# EK-TM4C1294XL_REV_D.net
KiCad netlist of a schematic drawn in EAGLE
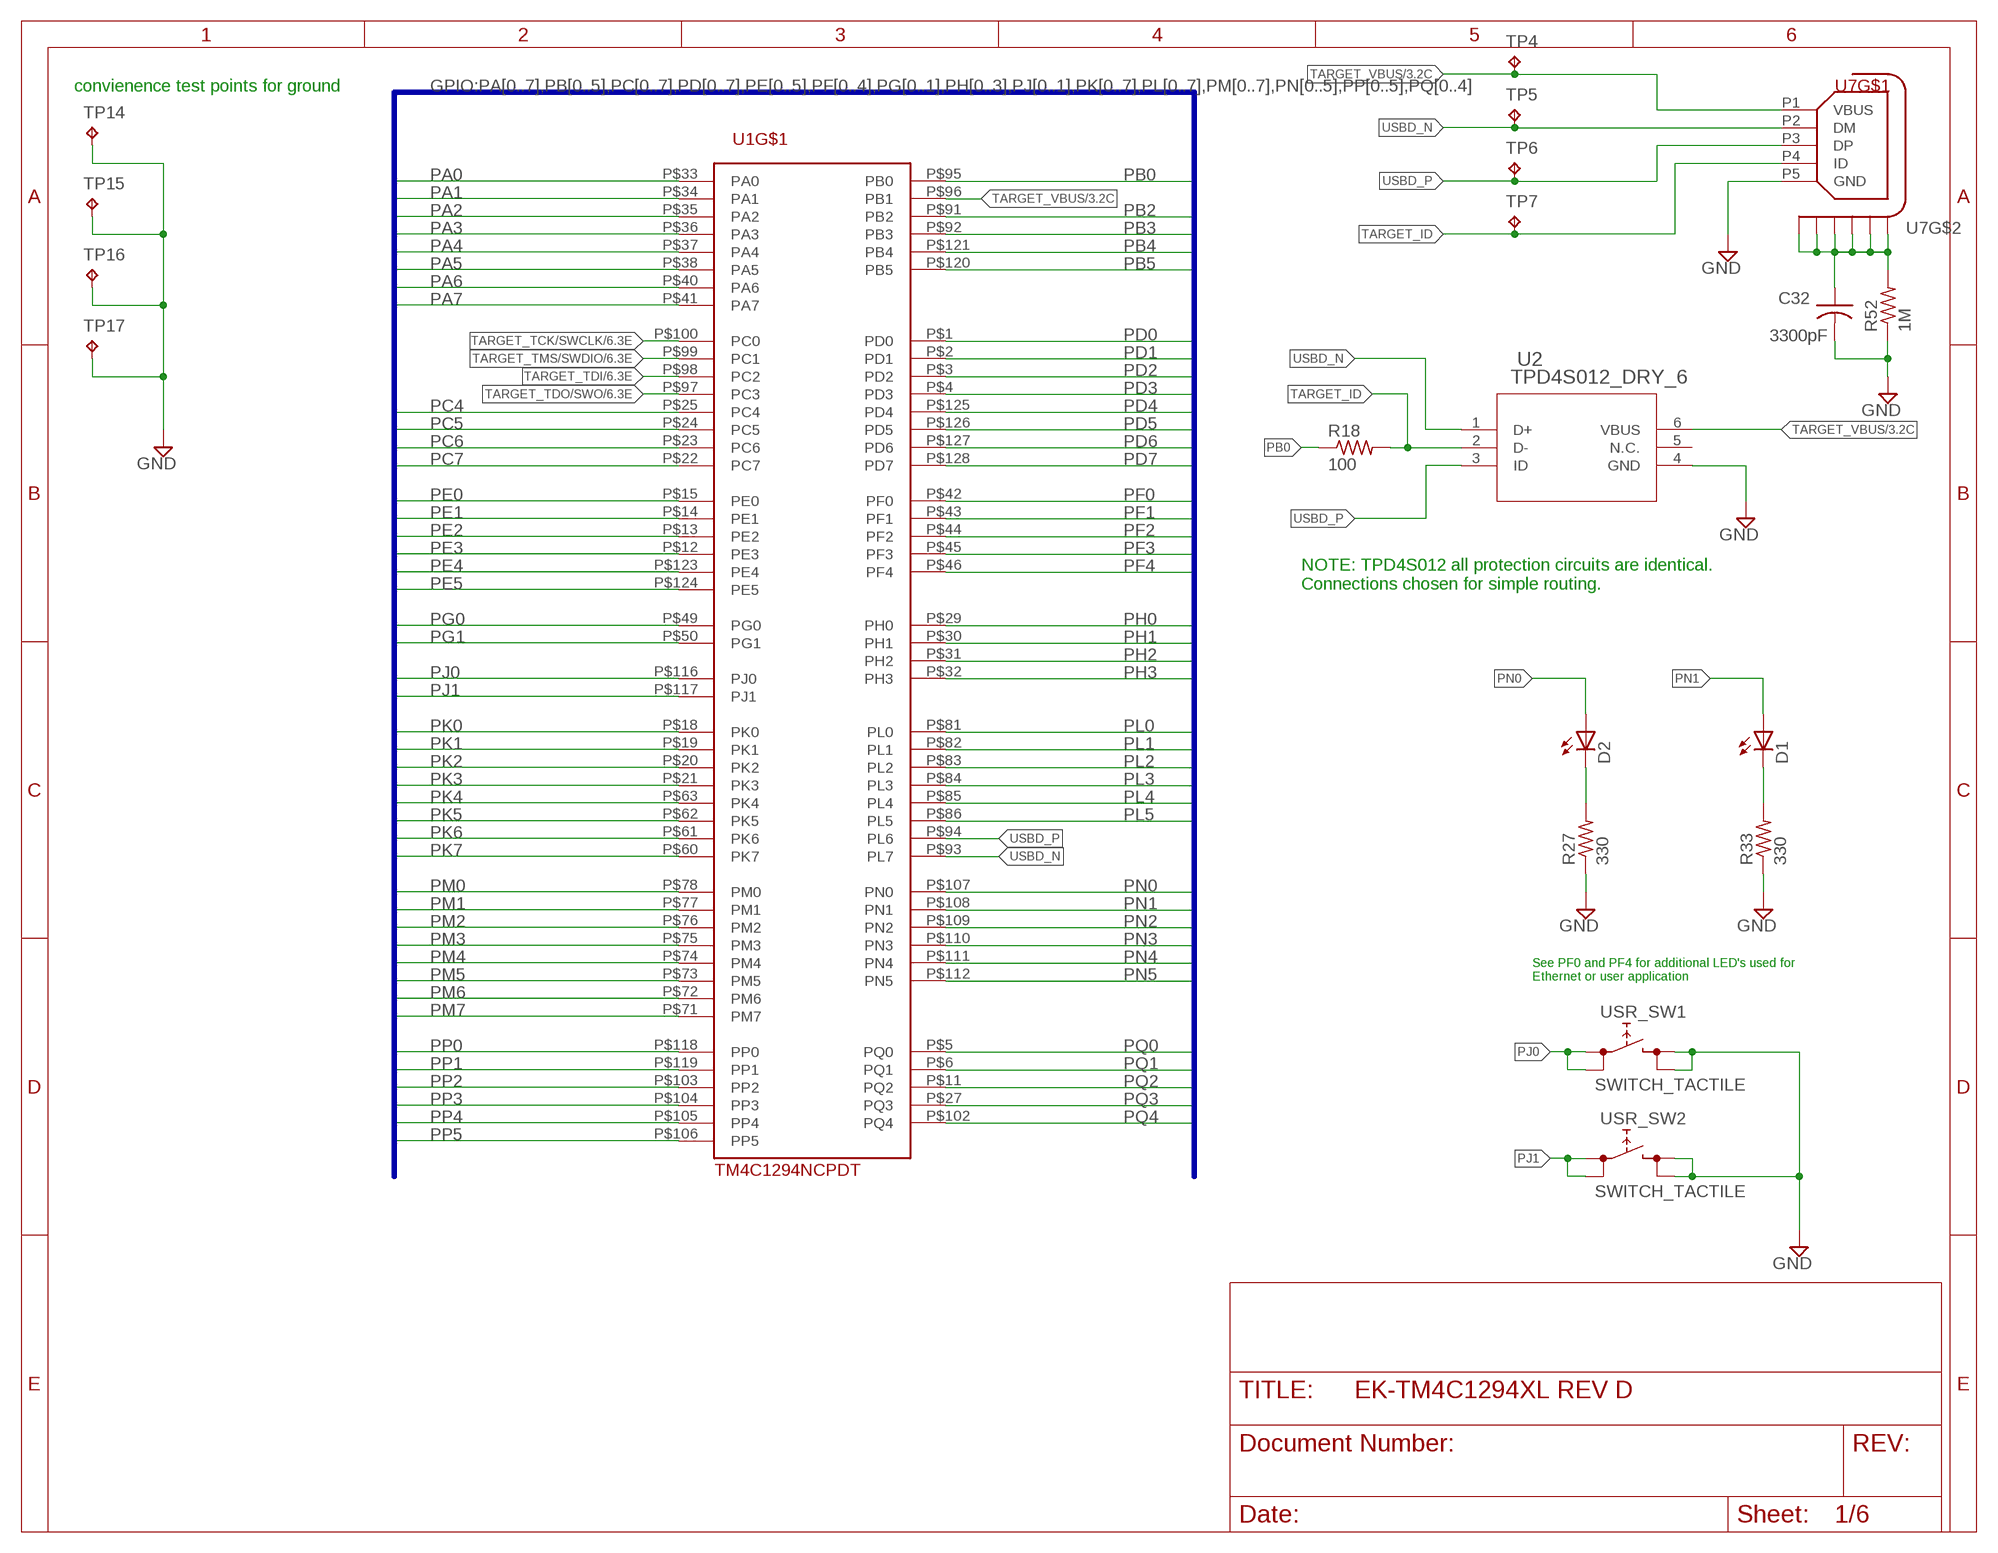
[diagram p0: schematic, sheet 1]
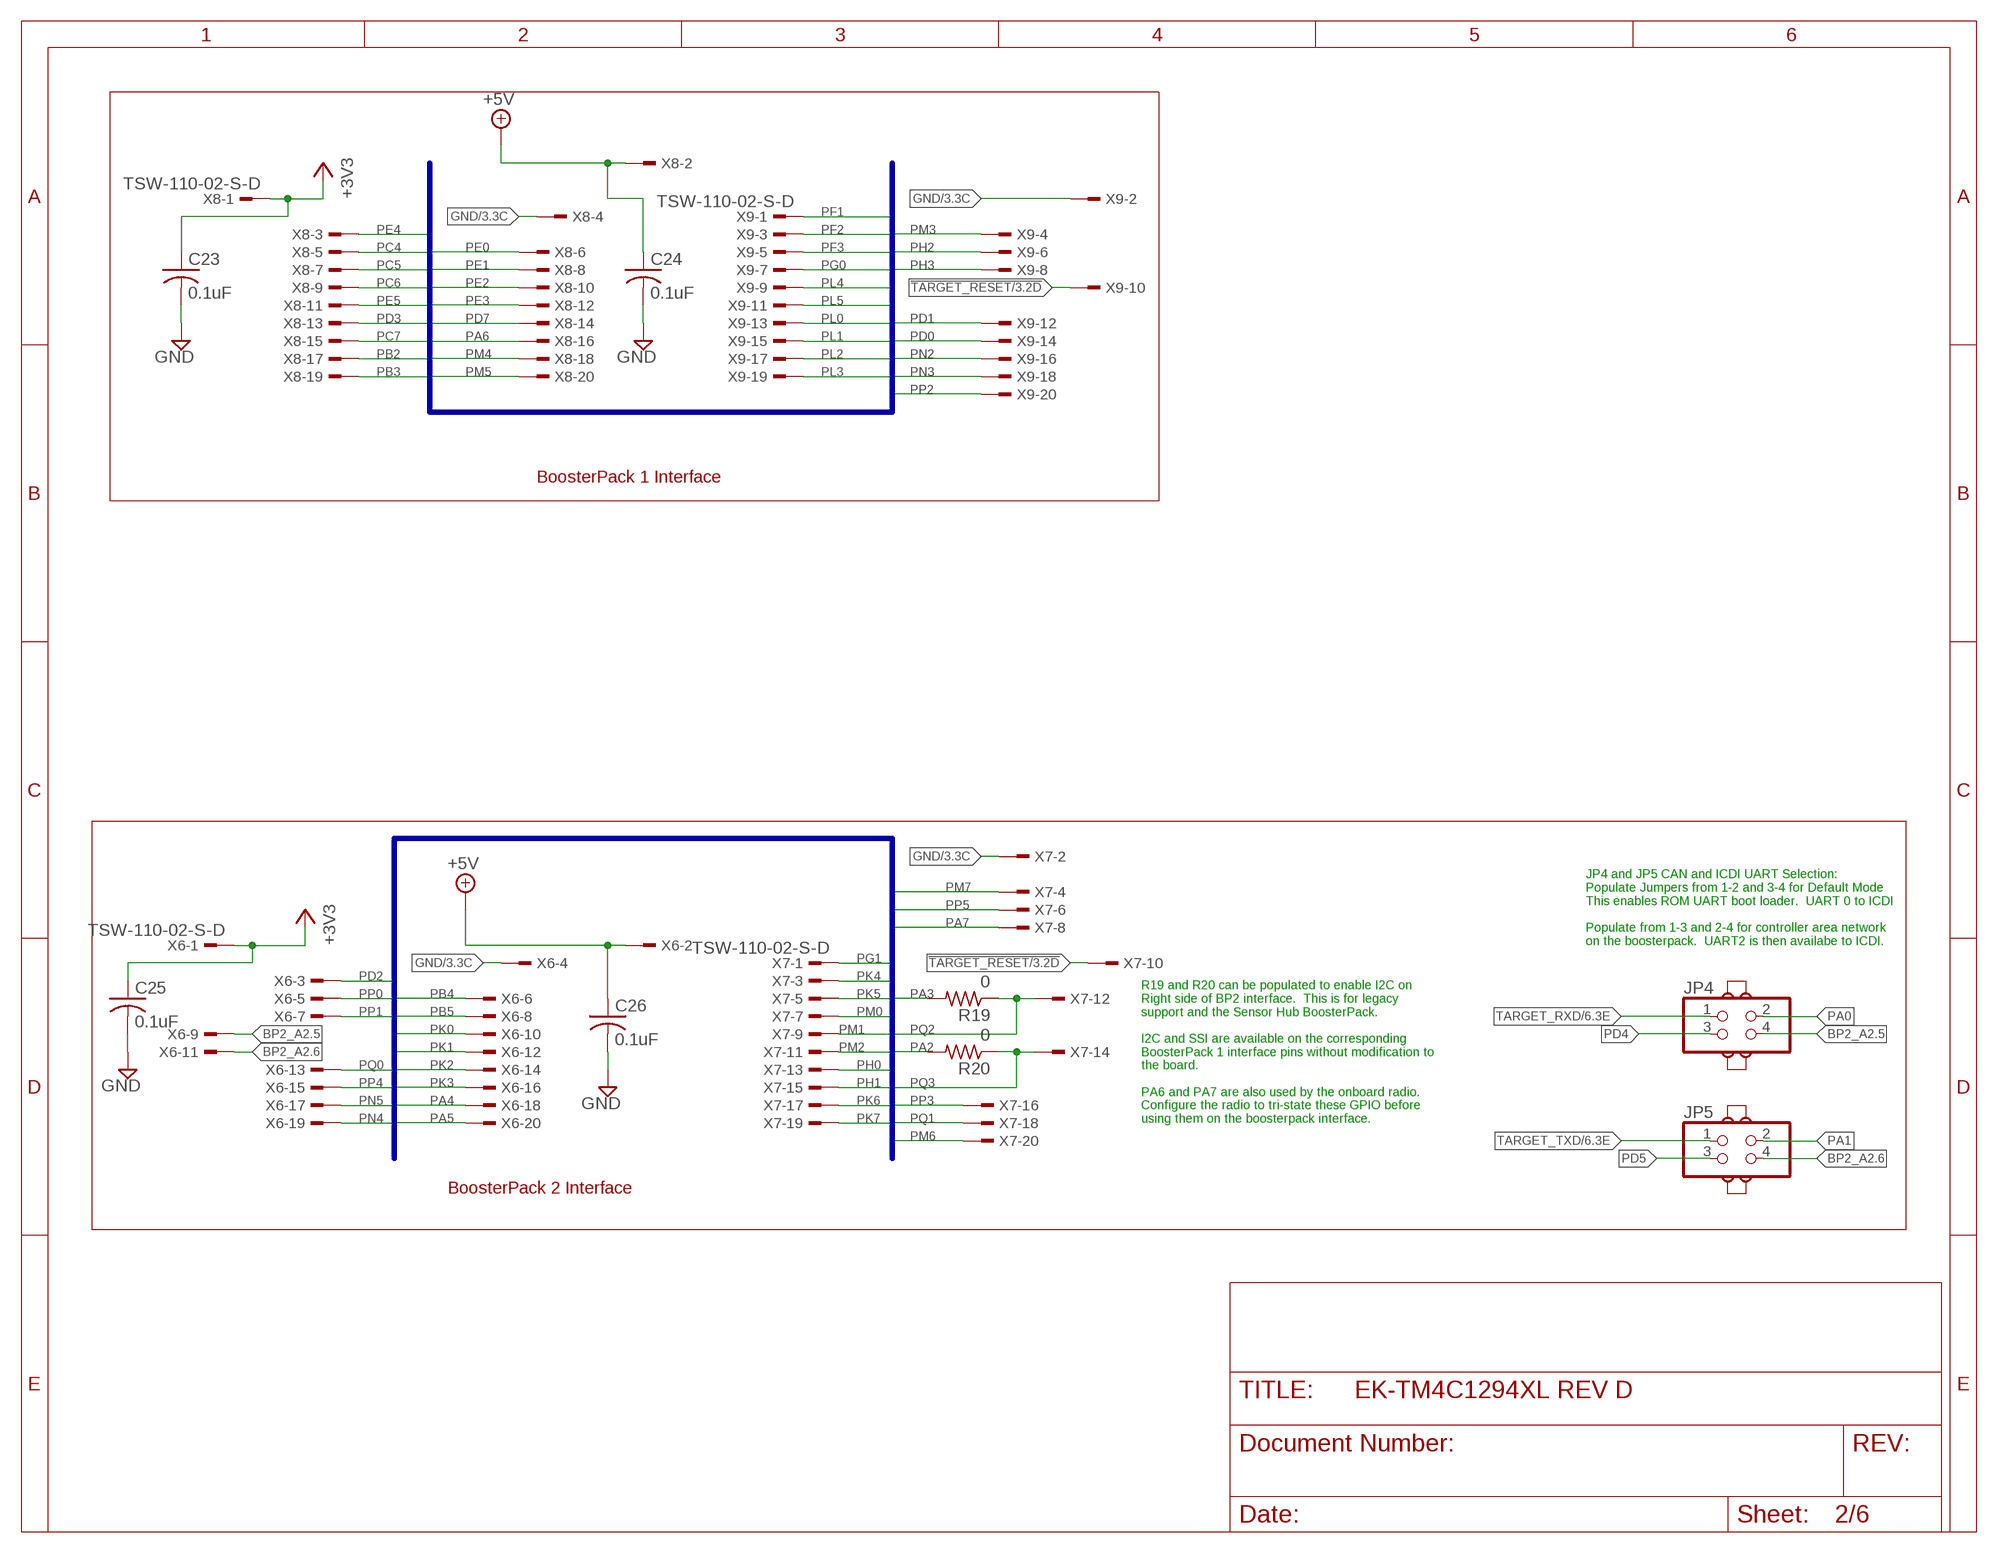
[diagram p1: schematic, sheet 2]
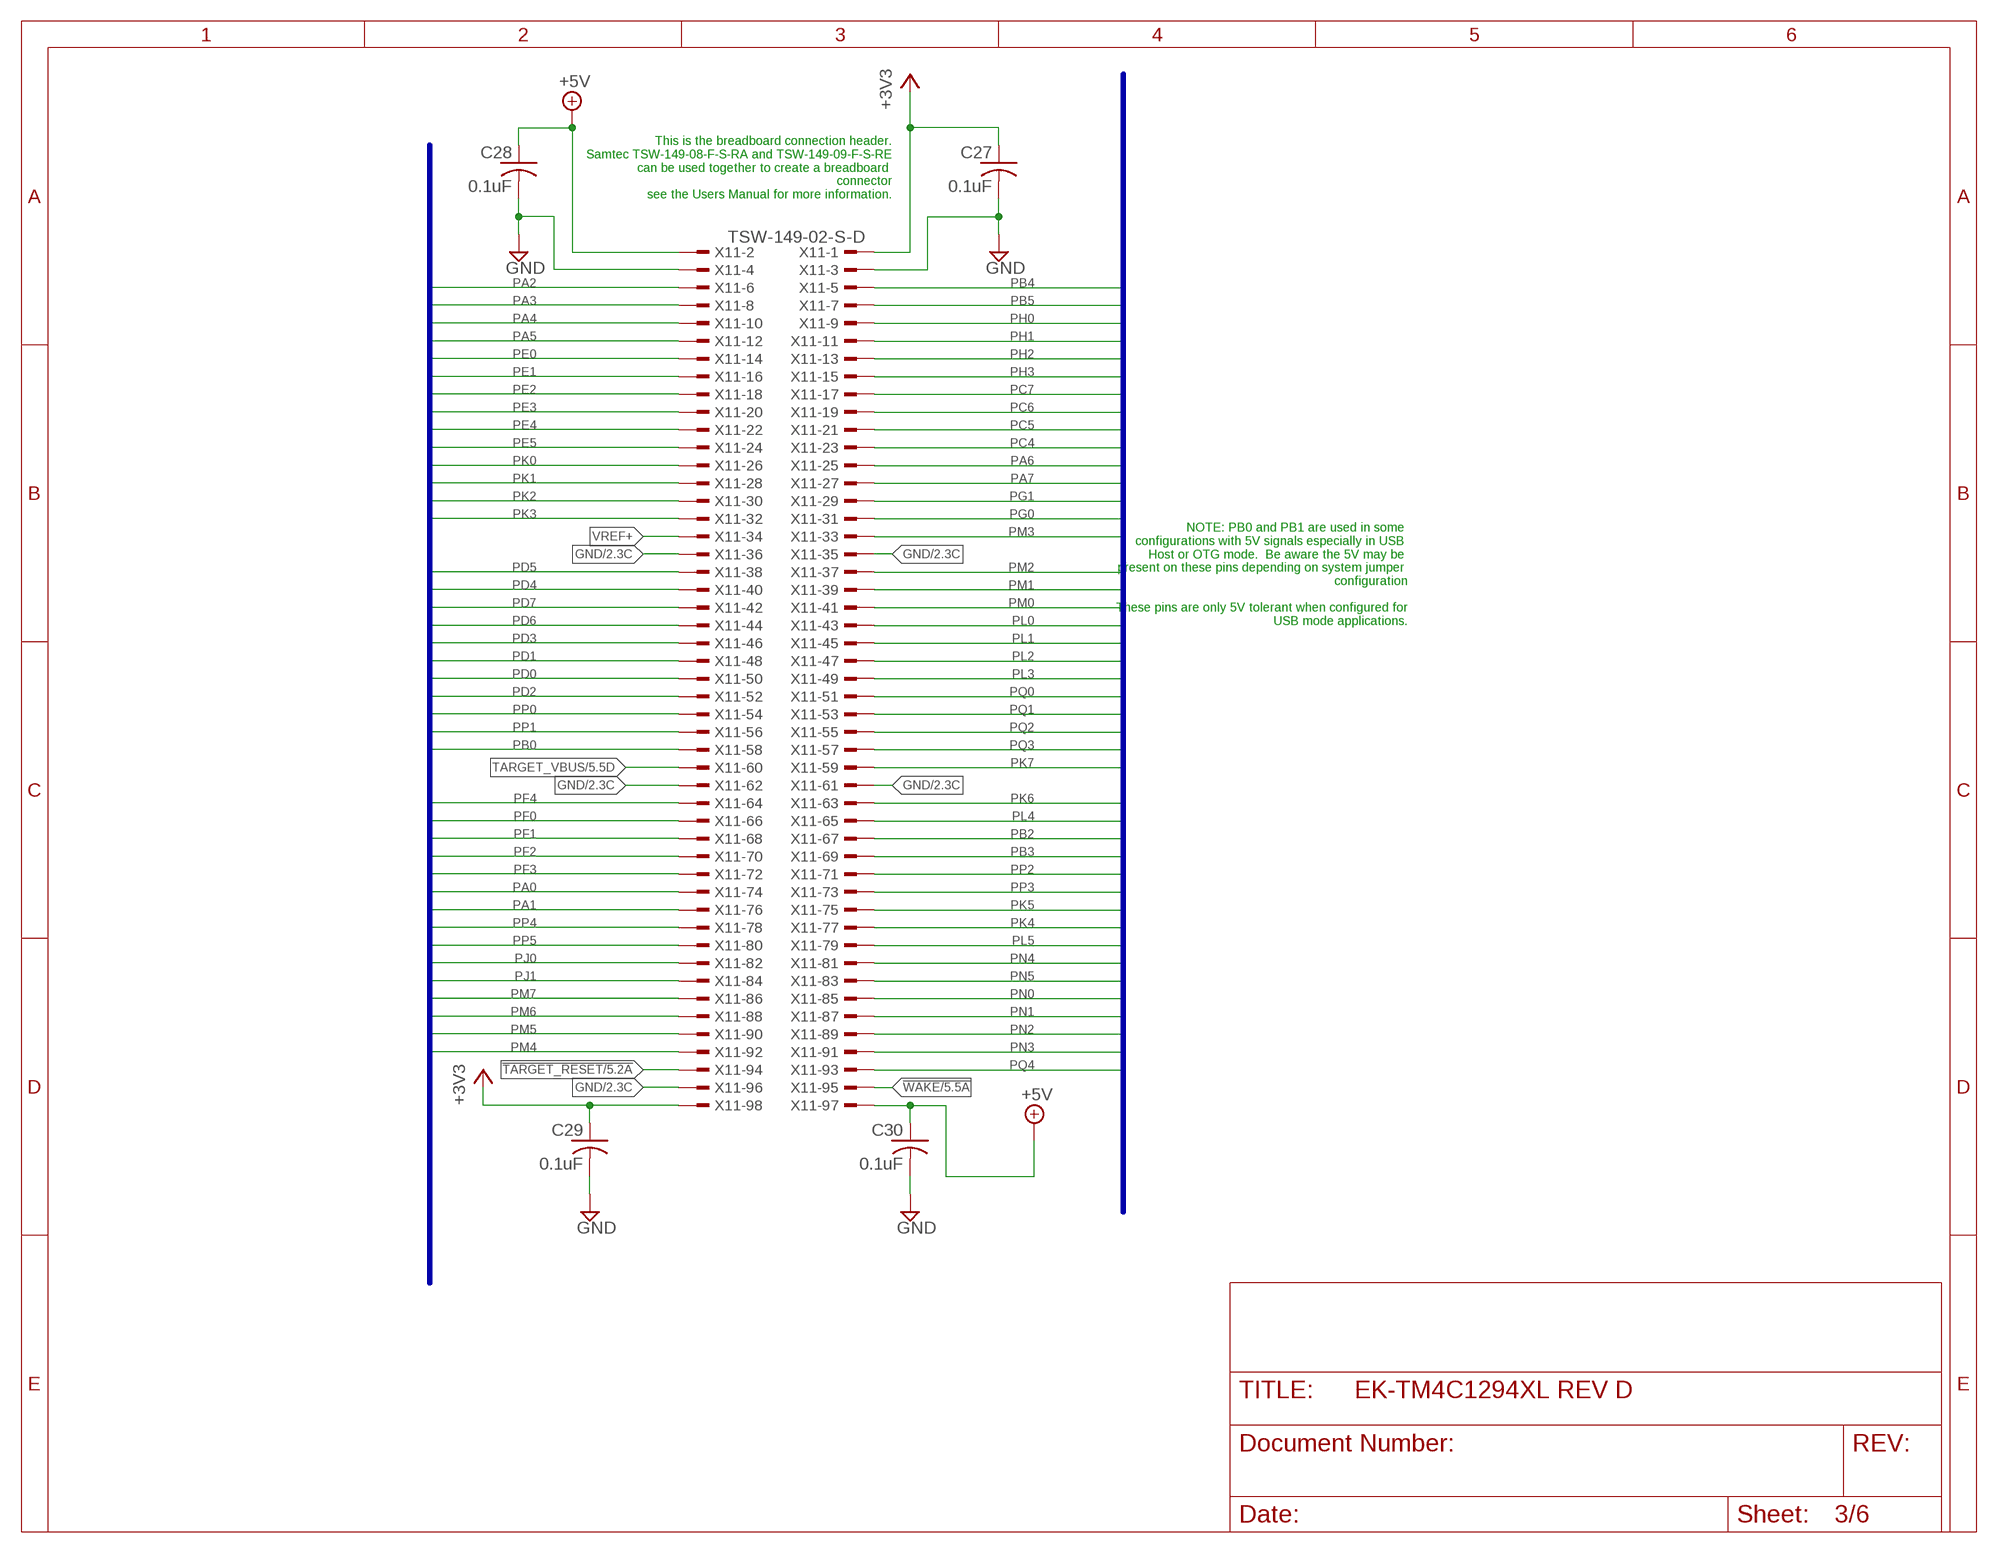
[diagram p2: schematic, sheet 3]
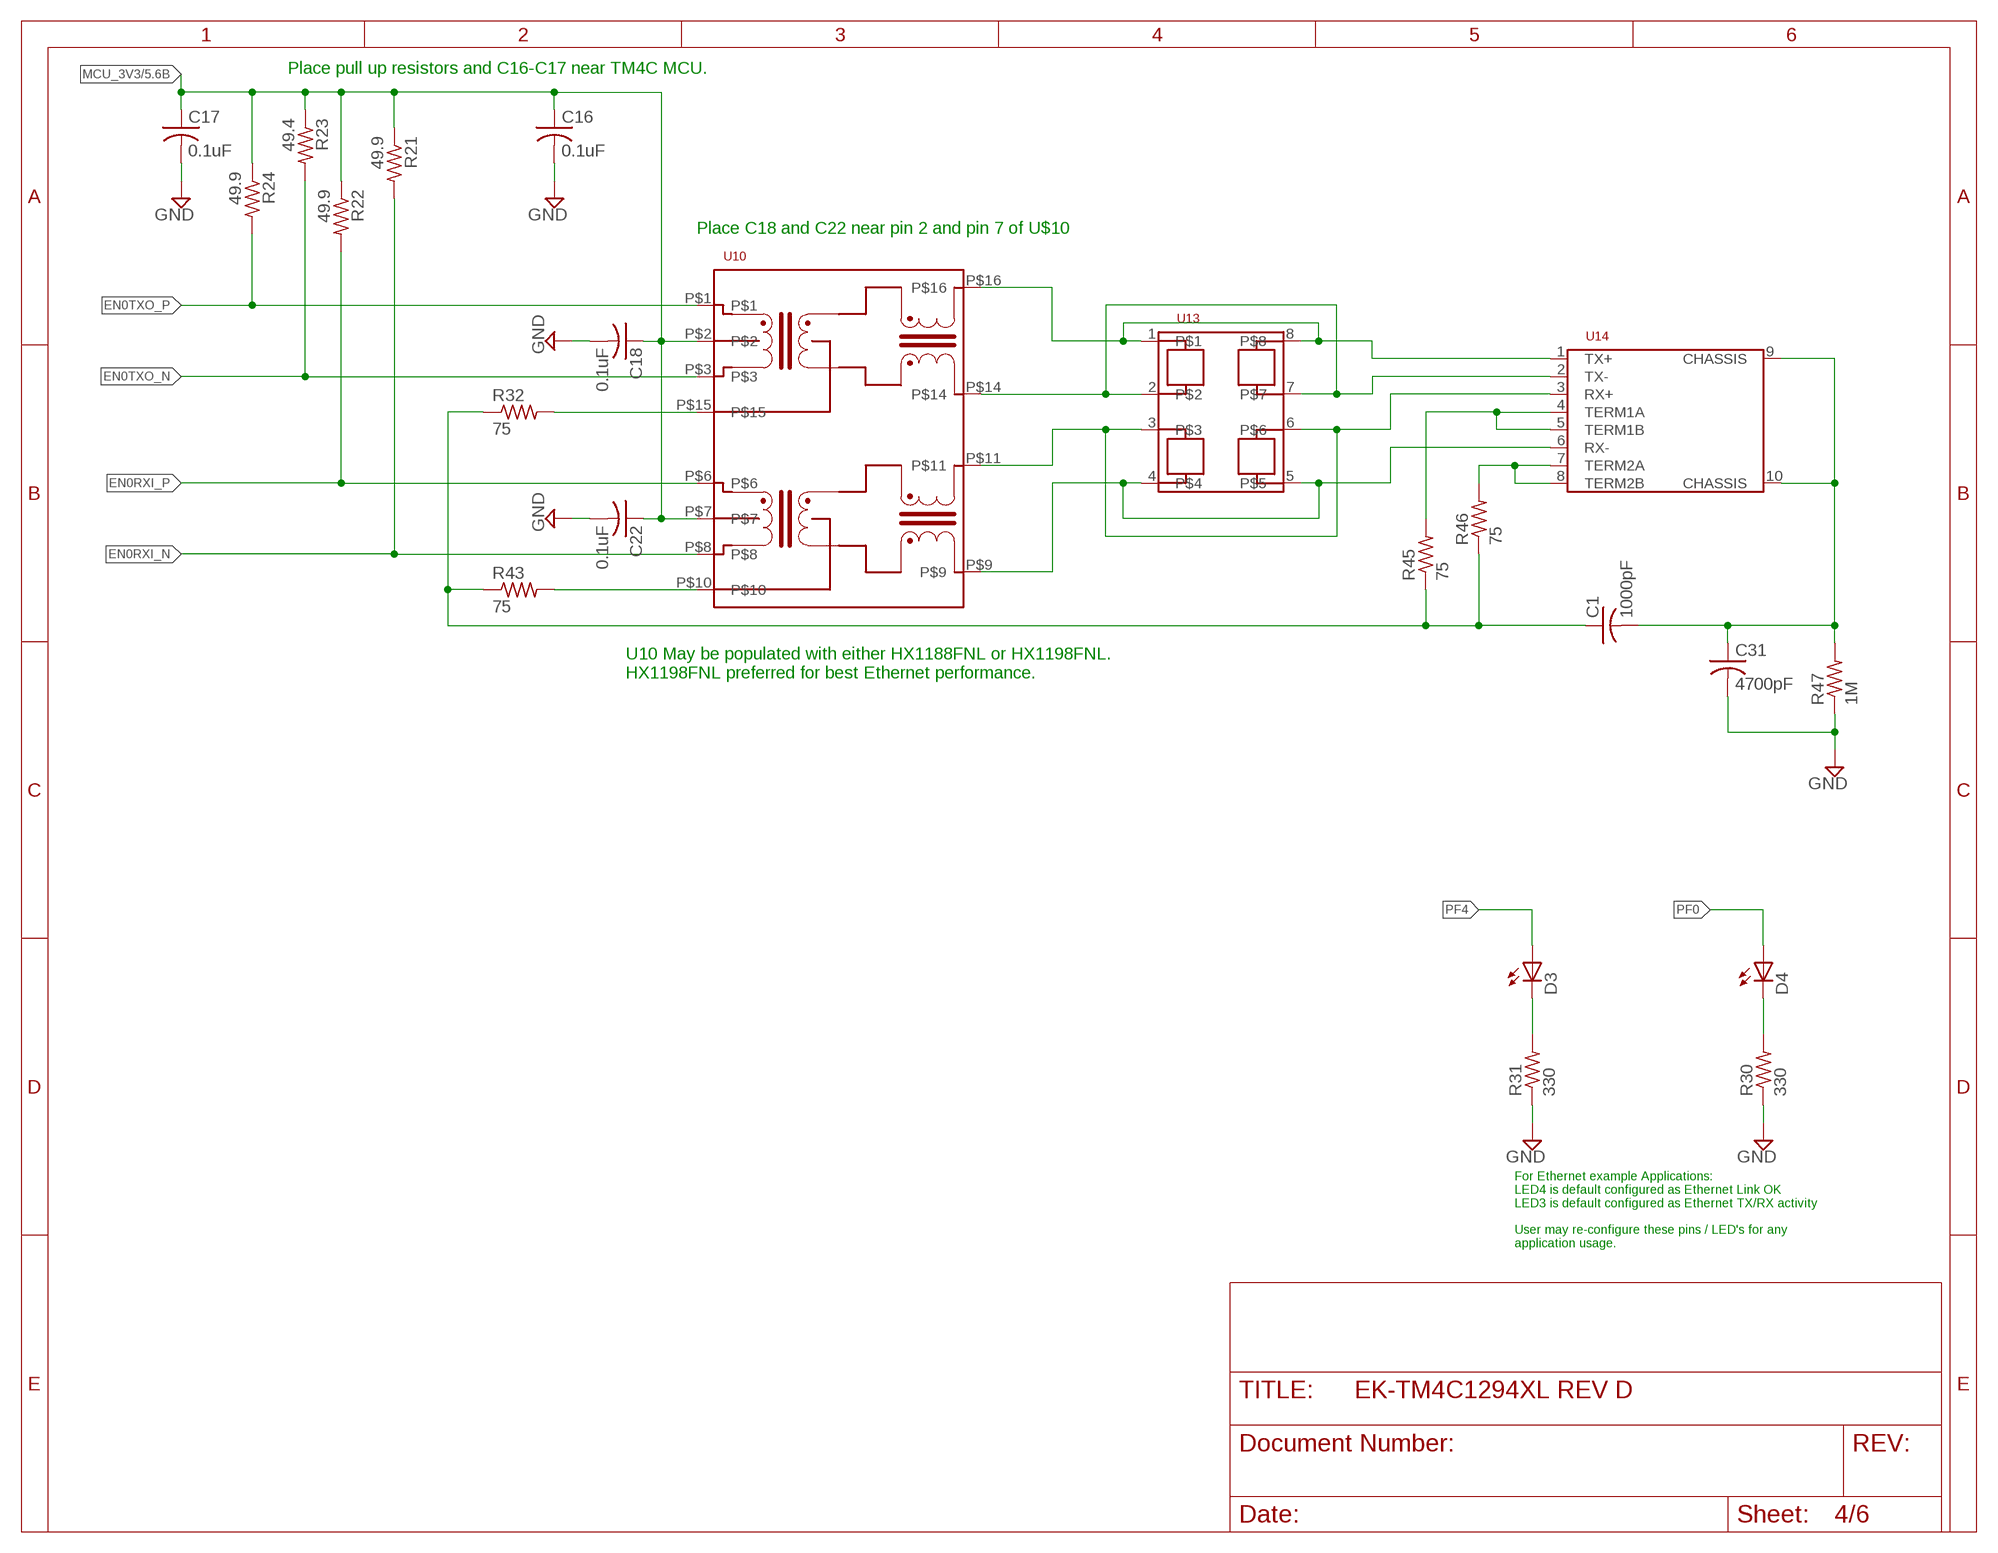
[diagram p3: schematic, sheet 4]
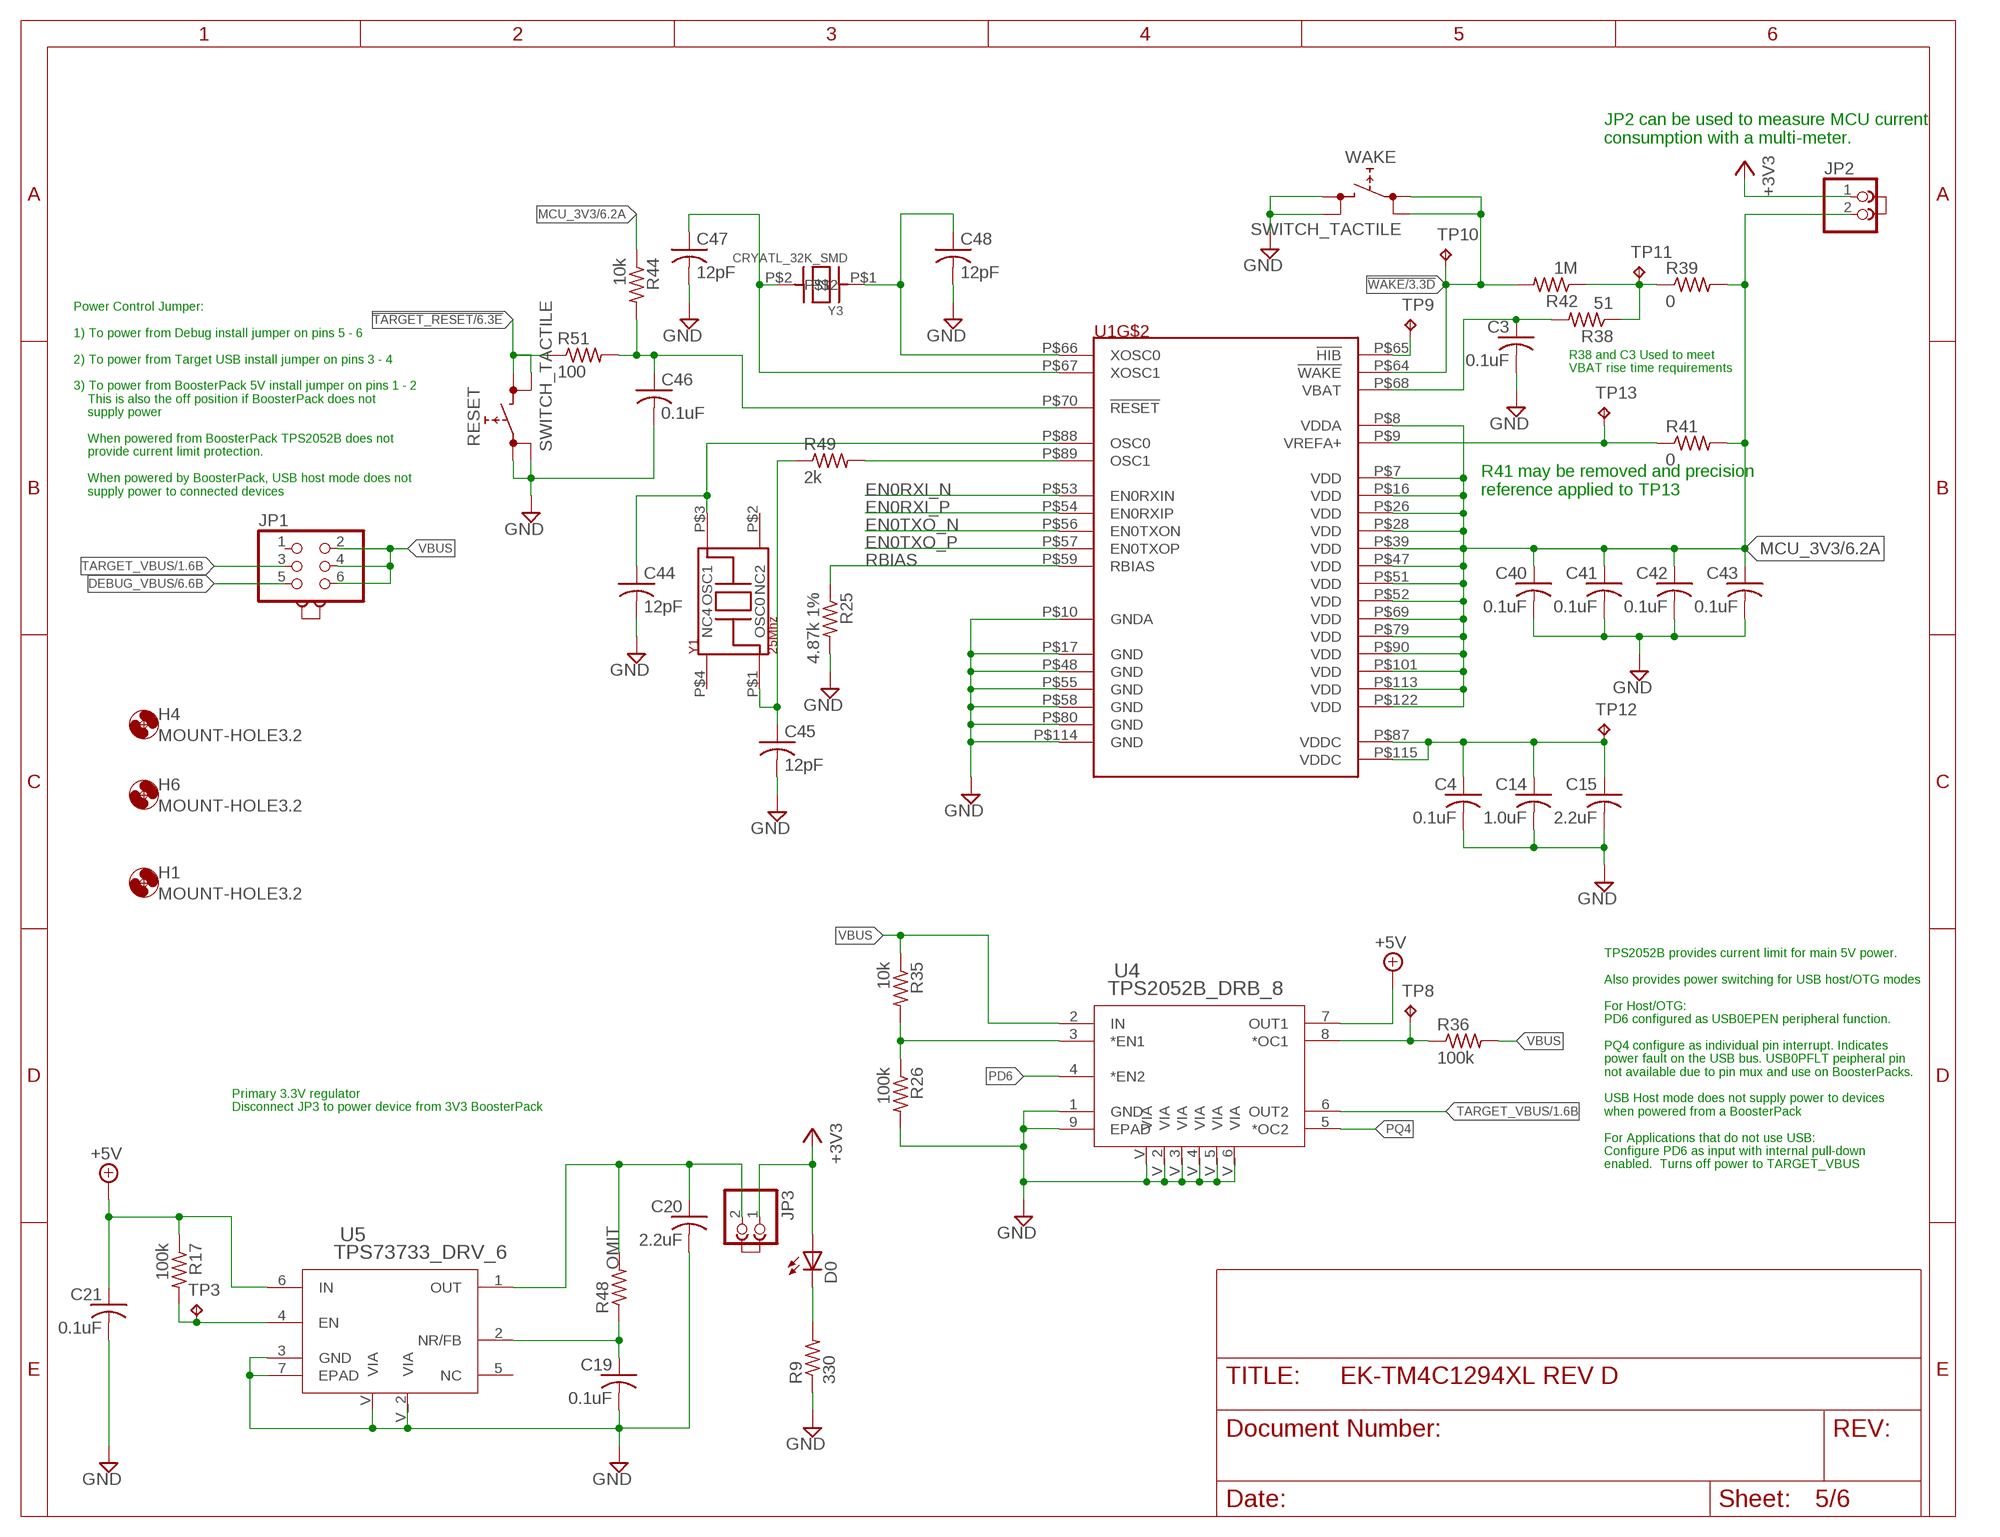
[diagram p4: schematic, sheet 5]
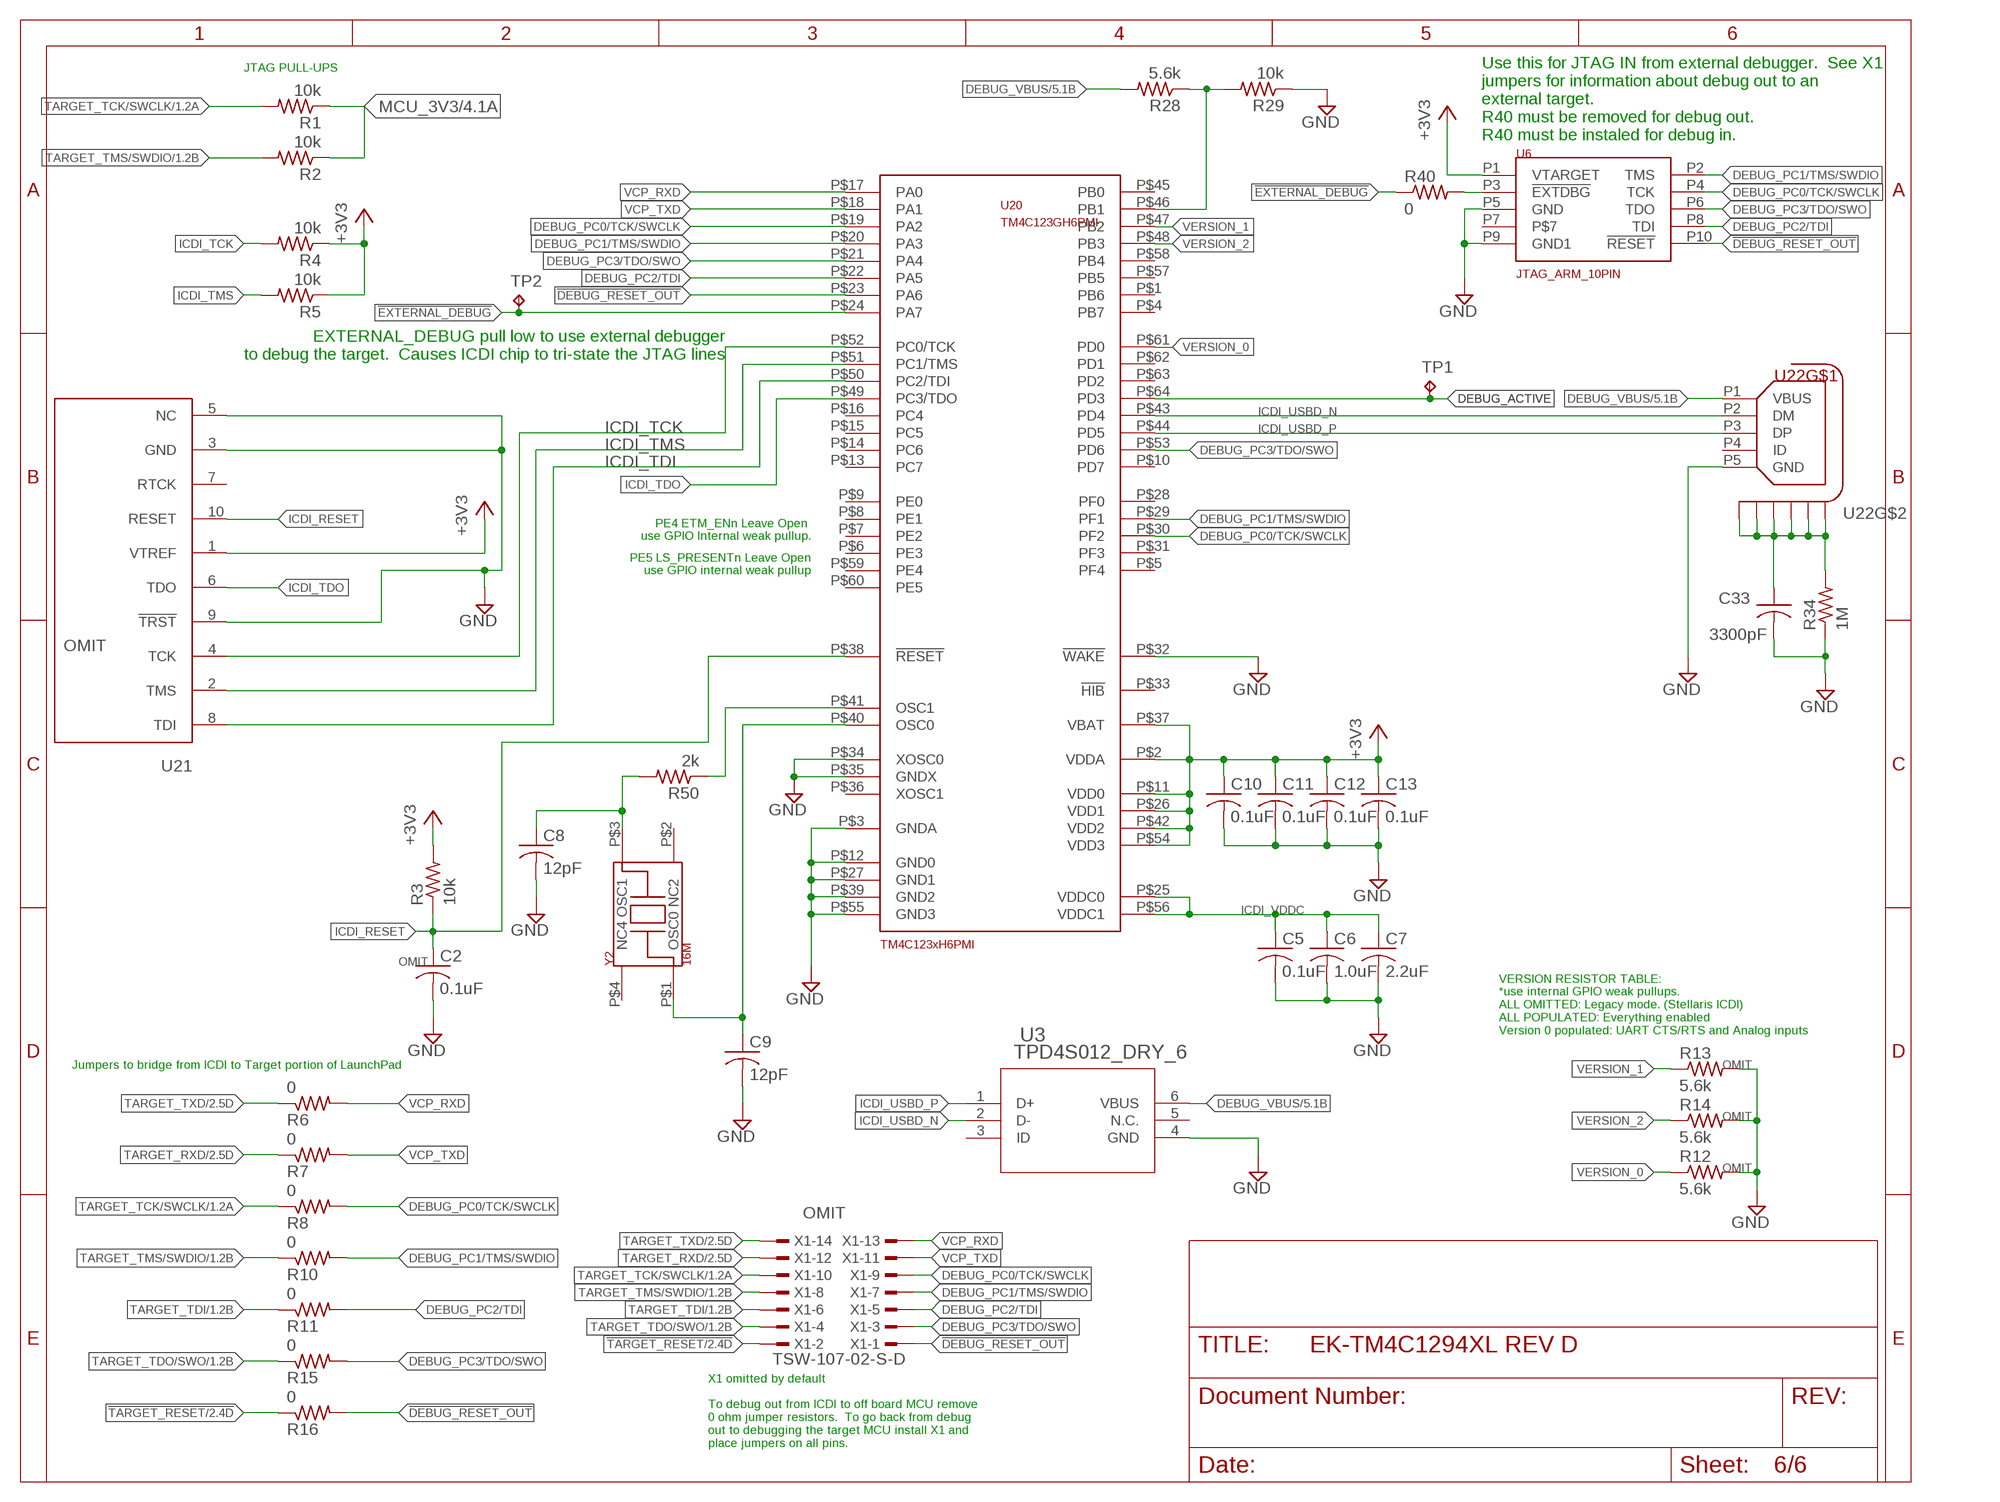
[diagram p5: schematic, sheet 6]

(export (version "E")
  (design (tool "Eeschema 10.0.6"))
  (components
    (comp (ref "C32")
      (value "3300pF")
      (footprint "eagle-import:C0603")
      (libsource (lib "eagle-import") (part "C-USC0603"))
    )
    (comp (ref "D1")
      (value "LEDCHIPLED_0603")
      (footprint "eagle-import:CHIPLED_0603")
      (libsource (lib "eagle-import") (part "LEDCHIPLED_0603"))
    )
    (comp (ref "D2")
      (value "LEDCHIPLED_0603")
      (footprint "eagle-import:CHIPLED_0603")
      (libsource (lib "eagle-import") (part "LEDCHIPLED_0603"))
    )
    (comp (ref "R18")
      (value "100")
      (footprint "eagle-import:R0402")
      (libsource (lib "eagle-import") (part "ek-tm4c129exl_R-US_R0402"))
    )
    (comp (ref "R27")
      (value "330")
      (footprint "eagle-import:R0402")
      (libsource (lib "eagle-import") (part "ek-tm4c129exl_R-US_R0402"))
    )
    (comp (ref "R33")
      (value "330")
      (footprint "eagle-import:R0402")
      (libsource (lib "eagle-import") (part "ek-tm4c129exl_R-US_R0402"))
    )
    (comp (ref "R52")
      (value "1M")
      (footprint "eagle-import:R0603")
      (libsource (lib "eagle-import") (part "R-US_R0603"))
    )
    (comp (ref "TP4")
      (value "TPPAD1-13")
      (footprint "eagle-import:P1-13")
      (libsource (lib "eagle-import") (part "TPPAD1-13"))
    )
    (comp (ref "TP5")
      (value "TPPAD1-13")
      (footprint "eagle-import:P1-13")
      (libsource (lib "eagle-import") (part "TPPAD1-13"))
    )
    (comp (ref "TP6")
      (value "TPPAD1-13")
      (footprint "eagle-import:P1-13")
      (libsource (lib "eagle-import") (part "TPPAD1-13"))
    )
    (comp (ref "TP7")
      (value "TPPAD1-13")
      (footprint "eagle-import:P1-13")
      (libsource (lib "eagle-import") (part "TPPAD1-13"))
    )
    (comp (ref "TP14")
      (value "TPPAD1-13")
      (footprint "eagle-import:P1-13")
      (libsource (lib "eagle-import") (part "TPPAD1-13"))
    )
    (comp (ref "TP15")
      (value "TPPAD1-13")
      (footprint "eagle-import:P1-13")
      (libsource (lib "eagle-import") (part "TPPAD1-13"))
    )
    (comp (ref "TP16")
      (value "TPPAD1-13")
      (footprint "eagle-import:P1-13")
      (libsource (lib "eagle-import") (part "TPPAD1-13"))
    )
    (comp (ref "TP17")
      (value "TPPAD1-13")
      (footprint "eagle-import:P1-13")
      (libsource (lib "eagle-import") (part "TPPAD1-13"))
    )
    (comp (ref "U1")
      (value "TM4C1294NCPDT")
      (footprint "eagle-import:TQFP-128")
      (fields (field (name "GNUM") "G50-QF128-C1294-ALH"))
      (libsource (lib "eagle-import") (part "TM4C1294NCPDT"))
    )
    (comp (ref "U2")
      (value "TPD4S012_DRY_6")
      (footprint "eagle-import:DRY6")
      (fields
        (field (name "GENERIC_PART_NUMBER") "TPD4S012")
        (field (name "MANUFACTURER") "Texas Instruments")
        (field (name "MANUFACTURER_PART_NUMBER") "tpd4s012_dry_6")
      )
      (libsource (lib "eagle-import") (part "TPD4S012_DRY_6"))
    )
    (comp (ref "U7")
      (value "CON_USB_HIROSE_MICRO_AB_ZX62D_AB_5P8")
      (footprint "eagle-import:CON_USB_MICRO_AB_HIROSE_ZX62D-AB-5P8")
      (fields (field (name "GNUM") "G20-USBU-THAB-CEB"))
      (libsource (lib "eagle-import") (part "CON_USB_HIROSE_MICRO_AB_ZX62D_AB_5P8"))
    )
    (comp (ref "USR_SW1")
      (value "SWITCH_TACTILE")
      (footprint "eagle-import:SWITCH_6MM_6MM_TE_CON_SMD")
      (libsource (lib "eagle-import") (part "SWITCH_TACTILE"))
    )
    (comp (ref "USR_SW2")
      (value "SWITCH_TACTILE")
      (footprint "eagle-import:SWITCH_6MM_6MM_TE_CON_SMD")
      (libsource (lib "eagle-import") (part "SWITCH_TACTILE"))
    )
    (comp (ref "C2")
      (value "0.1uF")
      (footprint "eagle-import:C0402")
      (fields (field (name "POPOP") "OMIT"))
      (libsource (lib "eagle-import") (part "ek-tm4c129exl_C-USC0402"))
    )
    (comp (ref "C5")
      (value "0.1uF")
      (footprint "eagle-import:C0402")
      (libsource (lib "eagle-import") (part "ek-tm4c129exl_C-USC0402"))
    )
    (comp (ref "C6")
      (value "1.0uF")
      (footprint "eagle-import:C0402")
      (libsource (lib "eagle-import") (part "ek-tm4c129exl_C-USC0402"))
    )
    (comp (ref "C7")
      (value "2.2uF")
      (footprint "eagle-import:C0603")
      (libsource (lib "eagle-import") (part "ek-tm4c129exl_C-USC0603"))
    )
    (comp (ref "C8")
      (value "12pF")
      (footprint "eagle-import:C0402")
      (libsource (lib "eagle-import") (part "ek-tm4c129exl_C-USC0402"))
    )
    (comp (ref "C9")
      (value "12pF")
      (footprint "eagle-import:C0402")
      (libsource (lib "eagle-import") (part "ek-tm4c129exl_C-USC0402"))
    )
    (comp (ref "C10")
      (value "0.1uF")
      (footprint "eagle-import:C0402")
      (libsource (lib "eagle-import") (part "ek-tm4c129exl_C-USC0402"))
    )
    (comp (ref "C11")
      (value "0.1uF")
      (footprint "eagle-import:C0402")
      (libsource (lib "eagle-import") (part "ek-tm4c129exl_C-USC0402"))
    )
    (comp (ref "C12")
      (value "0.1uF")
      (footprint "eagle-import:C0402")
      (libsource (lib "eagle-import") (part "ek-tm4c129exl_C-USC0402"))
    )
    (comp (ref "C13")
      (value "0.1uF")
      (footprint "eagle-import:C0402")
      (libsource (lib "eagle-import") (part "ek-tm4c129exl_C-USC0402"))
    )
    (comp (ref "C33")
      (value "3300pF")
      (footprint "eagle-import:C0603")
      (libsource (lib "eagle-import") (part "C-USC0603"))
    )
    (comp (ref "R1")
      (value "10k")
      (footprint "eagle-import:R0402")
      (libsource (lib "eagle-import") (part "ek-tm4c129exl_R-US_R0402"))
    )
    (comp (ref "R2")
      (value "10k")
      (footprint "eagle-import:R0402")
      (libsource (lib "eagle-import") (part "ek-tm4c129exl_R-US_R0402"))
    )
    (comp (ref "R3")
      (value "10k")
      (footprint "eagle-import:R0402")
      (libsource (lib "eagle-import") (part "ek-tm4c129exl_R-US_R0402"))
    )
    (comp (ref "R4")
      (value "10k")
      (footprint "eagle-import:R0402")
      (libsource (lib "eagle-import") (part "ek-tm4c129exl_R-US_R0402"))
    )
    (comp (ref "R5")
      (value "10k")
      (footprint "eagle-import:R0402")
      (libsource (lib "eagle-import") (part "ek-tm4c129exl_R-US_R0402"))
    )
    (comp (ref "R6")
      (value "0")
      (footprint "eagle-import:R0402")
      (libsource (lib "eagle-import") (part "ek-tm4c129exl_R-US_R0402"))
    )
    (comp (ref "R7")
      (value "0")
      (footprint "eagle-import:R0402")
      (libsource (lib "eagle-import") (part "ek-tm4c129exl_R-US_R0402"))
    )
    (comp (ref "R8")
      (value "0")
      (footprint "eagle-import:R0402")
      (libsource (lib "eagle-import") (part "ek-tm4c129exl_R-US_R0402"))
    )
    (comp (ref "R10")
      (value "0")
      (footprint "eagle-import:R0402")
      (libsource (lib "eagle-import") (part "ek-tm4c129exl_R-US_R0402"))
    )
    (comp (ref "R11")
      (value "0")
      (footprint "eagle-import:R0402")
      (libsource (lib "eagle-import") (part "ek-tm4c129exl_R-US_R0402"))
    )
    (comp (ref "R12")
      (value "5.6k")
      (footprint "eagle-import:R0402")
      (fields (field (name "POPOP") "OMIT"))
      (libsource (lib "eagle-import") (part "ek-tm4c129exl_R-US_R0402"))
    )
    (comp (ref "R13")
      (value "5.6k")
      (footprint "eagle-import:R0402")
      (fields (field (name "POPOP") "OMIT"))
      (libsource (lib "eagle-import") (part "ek-tm4c129exl_R-US_R0402"))
    )
    (comp (ref "R14")
      (value "5.6k")
      (footprint "eagle-import:R0402")
      (fields (field (name "POPOP") "OMIT"))
      (libsource (lib "eagle-import") (part "ek-tm4c129exl_R-US_R0402"))
    )
    (comp (ref "R15")
      (value "0")
      (footprint "eagle-import:R0402")
      (libsource (lib "eagle-import") (part "ek-tm4c129exl_R-US_R0402"))
    )
    (comp (ref "R16")
      (value "0")
      (footprint "eagle-import:R0402")
      (libsource (lib "eagle-import") (part "ek-tm4c129exl_R-US_R0402"))
    )
    (comp (ref "R28")
      (value "5.6k")
      (footprint "eagle-import:R0402")
      (libsource (lib "eagle-import") (part "ek-tm4c129exl_R-US_R0402"))
    )
    (comp (ref "R29")
      (value "10k")
      (footprint "eagle-import:R0402")
      (libsource (lib "eagle-import") (part "ek-tm4c129exl_R-US_R0402"))
    )
    (comp (ref "R34")
      (value "1M")
      (footprint "eagle-import:R0603")
      (libsource (lib "eagle-import") (part "R-US_R0603"))
    )
    (comp (ref "R40")
      (value "0")
      (footprint "eagle-import:R0402")
      (libsource (lib "eagle-import") (part "ek-tm4c129exl_R-US_R0402"))
    )
    (comp (ref "R50")
      (value "2k")
      (footprint "eagle-import:R0402")
      (libsource (lib "eagle-import") (part "ek-tm4c129exl_R-US_R0402"))
    )
    (comp (ref "TP1")
      (value "TPPAD1-13")
      (footprint "eagle-import:P1-13")
      (libsource (lib "eagle-import") (part "TPPAD1-13"))
    )
    (comp (ref "TP2")
      (value "TPPAD1-13")
      (footprint "eagle-import:P1-13")
      (libsource (lib "eagle-import") (part "TPPAD1-13"))
    )
    (comp (ref "U3")
      (value "TPD4S012_DRY_6")
      (footprint "eagle-import:DRY6")
      (fields
        (field (name "GENERIC_PART_NUMBER") "TPD4S012")
        (field (name "MANUFACTURER") "Texas Instruments")
        (field (name "MANUFACTURER_PART_NUMBER") "tpd4s012_dry_6")
      )
      (libsource (lib "eagle-import") (part "TPD4S012_DRY_6"))
    )
    (comp (ref "U6")
      (value "JTAG_ARM_10PIN")
      (footprint "eagle-import:CON_2X5_50MIL")
      (libsource (lib "eagle-import") (part "JTAG_ARM_10PIN"))
    )
    (comp (ref "U20")
      (value "TM4C123GH6PMI")
      (footprint "eagle-import:LQFP-64-PM")
      (libsource (lib "eagle-import") (part "TM4C123GH6PMI"))
    )
    (comp (ref "U21")
      (value "TC2050-NL-MCP-NL")
      (footprint "eagle-import:TC2030-MCP-NL")
      (fields (field (name "POPOP") "OMIT"))
      (libsource (lib "eagle-import") (part "TC2050-NL-MCP-NL"))
    )
    (comp (ref "U22")
      (value "CON_USB_FCI_MICRO_B_10118194")
      (footprint "eagle-import:CON_USB_MICRO_B_FCI_10118194")
      (fields (field (name "GNUM") "G20-USBU-THB-CEB"))
      (libsource (lib "eagle-import") (part "CON_USB_FCI_MICRO_B_10118194"))
    )
    (comp (ref "X1")
      (value "TSW-107-02-S-D")
      (footprint "eagle-import:TSW-107-02-S-D")
      (fields (field (name "GNUM") "G22-THVEU-2X7P-BAB") (field (name "POPOP") "OMIT"))
      (libsource (lib "eagle-import") (part "TSW-107-02-S-D"))
    )
    (comp (ref "Y2")
      (value "16M")
      (footprint "eagle-import:NDK3.2X2.5")
      (libsource (lib "eagle-import") (part "NX3225GA"))
    )
    (comp (ref "C1")
      (value "1000pF")
      (footprint "eagle-import:C1210")
      (libsource (lib "eagle-import") (part "C-USC1210"))
    )
    (comp (ref "C16")
      (value "0.1uF")
      (footprint "eagle-import:C0402")
      (libsource (lib "eagle-import") (part "ek-tm4c129exl_C-USC0402"))
    )
    (comp (ref "C17")
      (value "0.1uF")
      (footprint "eagle-import:C0402")
      (libsource (lib "eagle-import") (part "ek-tm4c129exl_C-USC0402"))
    )
    (comp (ref "C18")
      (value "0.1uF")
      (footprint "eagle-import:C0402")
      (libsource (lib "eagle-import") (part "ek-tm4c129exl_C-USC0402"))
    )
    (comp (ref "C22")
      (value "0.1uF")
      (footprint "eagle-import:C0402")
      (libsource (lib "eagle-import") (part "ek-tm4c129exl_C-USC0402"))
    )
    (comp (ref "C31")
      (value "4700pF")
      (footprint "eagle-import:C1812")
      (libsource (lib "eagle-import") (part "ek-tm4c129exl_C-USC1812"))
    )
    (comp (ref "D3")
      (value "LEDCHIPLED_0603")
      (footprint "eagle-import:CHIPLED_0603")
      (libsource (lib "eagle-import") (part "LEDCHIPLED_0603"))
    )
    (comp (ref "D4")
      (value "LEDCHIPLED_0603")
      (footprint "eagle-import:CHIPLED_0603")
      (libsource (lib "eagle-import") (part "LEDCHIPLED_0603"))
    )
    (comp (ref "R21")
      (value "49.9")
      (footprint "eagle-import:R0402")
      (libsource (lib "eagle-import") (part "ek-tm4c129exl_R-US_R0402"))
    )
    (comp (ref "R22")
      (value "49.9")
      (footprint "eagle-import:R0402")
      (libsource (lib "eagle-import") (part "ek-tm4c129exl_R-US_R0402"))
    )
    (comp (ref "R23")
      (value "49.4")
      (footprint "eagle-import:R0402")
      (libsource (lib "eagle-import") (part "ek-tm4c129exl_R-US_R0402"))
    )
    (comp (ref "R24")
      (value "49.9")
      (footprint "eagle-import:R0402")
      (libsource (lib "eagle-import") (part "ek-tm4c129exl_R-US_R0402"))
    )
    (comp (ref "R30")
      (value "330")
      (footprint "eagle-import:R0402")
      (libsource (lib "eagle-import") (part "ek-tm4c129exl_R-US_R0402"))
    )
    (comp (ref "R31")
      (value "330")
      (footprint "eagle-import:R0402")
      (libsource (lib "eagle-import") (part "ek-tm4c129exl_R-US_R0402"))
    )
    (comp (ref "R32")
      (value "75")
      (footprint "eagle-import:R0402")
      (libsource (lib "eagle-import") (part "ek-tm4c129exl_R-US_R0402"))
    )
    (comp (ref "R43")
      (value "75")
      (footprint "eagle-import:R0402")
      (libsource (lib "eagle-import") (part "ek-tm4c129exl_R-US_R0402"))
    )
    (comp (ref "R45")
      (value "75")
      (footprint "eagle-import:R0402")
      (libsource (lib "eagle-import") (part "ek-tm4c129exl_R-US_R0402"))
    )
    (comp (ref "R46")
      (value "75")
      (footprint "eagle-import:R0402")
      (libsource (lib "eagle-import") (part "ek-tm4c129exl_R-US_R0402"))
    )
    (comp (ref "R47")
      (value "1M")
      (footprint "eagle-import:R1206")
      (libsource (lib "eagle-import") (part "R-US_R1206"))
    )
    (comp (ref "U10")
      (value "MAG_PULSE_HX1188FNL")
      (footprint "eagle-import:MAG_PULSE_HX1188FNL")
      (libsource (lib "eagle-import") (part "MAG_PULSE_HX1188FNL"))
    )
    (comp (ref "U13")
      (value "SLVU2.8-4")
      (footprint "eagle-import:D8")
      (libsource (lib "eagle-import") (part "SLVU2.8-4"))
    )
    (comp (ref "U14")
      (value "JACK_RJ45_NOMAG_NOLED_TECON")
      (footprint "eagle-import:RJ45_TE_CON_NOMAG_NOLED")
      (libsource (lib "eagle-import") (part "JACK_RJ45_NOMAG_NOLED_TECON"))
    )
    (comp (ref "C23")
      (value "0.1uF")
      (footprint "eagle-import:C0402")
      (libsource (lib "eagle-import") (part "ek-tm4c129exl_C-USC0402"))
    )
    (comp (ref "C24")
      (value "0.1uF")
      (footprint "eagle-import:C0402")
      (libsource (lib "eagle-import") (part "ek-tm4c129exl_C-USC0402"))
    )
    (comp (ref "C25")
      (value "0.1uF")
      (footprint "eagle-import:C0402")
      (libsource (lib "eagle-import") (part "ek-tm4c129exl_C-USC0402"))
    )
    (comp (ref "C26")
      (value "0.1uF")
      (footprint "eagle-import:C0402")
      (libsource (lib "eagle-import") (part "ek-tm4c129exl_C-USC0402"))
    )
    (comp (ref "J4")
      (value "JUMPER")
      (footprint "eagle-import:JUMP")
      (libsource (lib "eagle-import") (part "JUMPER"))
    )
    (comp (ref "J5")
      (value "JUMPER")
      (footprint "eagle-import:JUMP")
      (libsource (lib "eagle-import") (part "JUMPER"))
    )
    (comp (ref "J6")
      (value "JUMPER")
      (footprint "eagle-import:JUMP")
      (libsource (lib "eagle-import") (part "JUMPER"))
    )
    (comp (ref "J7")
      (value "JUMPER")
      (footprint "eagle-import:JUMP")
      (libsource (lib "eagle-import") (part "JUMPER"))
    )
    (comp (ref "JP4")
      (value "PINHD-2X2")
      (footprint "eagle-import:2X02")
      (libsource (lib "eagle-import") (part "PINHD-2X2"))
    )
    (comp (ref "JP5")
      (value "PINHD-2X2")
      (footprint "eagle-import:2X02")
      (libsource (lib "eagle-import") (part "PINHD-2X2"))
    )
    (comp (ref "R19")
      (value "0")
      (footprint "eagle-import:R0402")
      (libsource (lib "eagle-import") (part "ek-tm4c129exl_R-US_R0402"))
    )
    (comp (ref "R20")
      (value "0")
      (footprint "eagle-import:R0402")
      (libsource (lib "eagle-import") (part "ek-tm4c129exl_R-US_R0402"))
    )
    (comp (ref "X6")
      (value "TSW-110-02-S-D")
      (footprint "eagle-import:TSW-110-02-S-D")
      (fields (field (name "GNUM") "G22-THSTK-2X10-BAC"))
      (libsource (lib "eagle-import") (part "TSW-110-02-S-D"))
    )
    (comp (ref "X7")
      (value "TSW-110-02-S-D")
      (footprint "eagle-import:TSW-110-02-S-D")
      (fields (field (name "GNUM") "G22-THSTK-2X10-BAC"))
      (libsource (lib "eagle-import") (part "TSW-110-02-S-D"))
    )
    (comp (ref "X8")
      (value "TSW-110-02-S-D")
      (footprint "eagle-import:TSW-110-02-S-D")
      (fields (field (name "GNUM") "G22-THSTK-2X10-BAC"))
      (libsource (lib "eagle-import") (part "TSW-110-02-S-D"))
    )
    (comp (ref "X9")
      (value "TSW-110-02-S-D")
      (footprint "eagle-import:TSW-110-02-S-D")
      (fields (field (name "GNUM") "G22-THSTK-2X10-BAC"))
      (libsource (lib "eagle-import") (part "TSW-110-02-S-D"))
    )
    (comp (ref "C27")
      (value "0.1uF")
      (footprint "eagle-import:C0402")
      (libsource (lib "eagle-import") (part "ek-tm4c129exl_C-USC0402"))
    )
    (comp (ref "C28")
      (value "0.1uF")
      (footprint "eagle-import:C0402")
      (libsource (lib "eagle-import") (part "ek-tm4c129exl_C-USC0402"))
    )
    (comp (ref "C29")
      (value "0.1uF")
      (footprint "eagle-import:C0402")
      (libsource (lib "eagle-import") (part "ek-tm4c129exl_C-USC0402"))
    )
    (comp (ref "C30")
      (value "0.1uF")
      (footprint "eagle-import:C0402")
      (libsource (lib "eagle-import") (part "ek-tm4c129exl_C-USC0402"))
    )
    (comp (ref "X11")
      (value "TSW-149-02-S-D")
      (footprint "eagle-import:TSW-149-02-S-D")
      (fields
        (field (name "GNUM1") "G22-THRE-1x49-AAC")
        (field (name "GNUM2") "G22-THRA-1X49-AAC")
        (field (name "POPOP") "OMIT")
      )
      (libsource (lib "eagle-import") (part "TSW-149-02-S-D"))
    )
    (comp (ref "C3")
      (value "0.1uF")
      (footprint "eagle-import:C0402")
      (libsource (lib "eagle-import") (part "ek-tm4c129exl_C-USC0402"))
    )
    (comp (ref "C4")
      (value "0.1uF")
      (footprint "eagle-import:C0402")
      (libsource (lib "eagle-import") (part "ek-tm4c129exl_C-USC0402"))
    )
    (comp (ref "C14")
      (value "1.0uF")
      (footprint "eagle-import:C0402")
      (libsource (lib "eagle-import") (part "ek-tm4c129exl_C-USC0402"))
    )
    (comp (ref "C15")
      (value "2.2uF")
      (footprint "eagle-import:C0603K")
      (fields (field (name "DIGIKEY_PARTNUM") "311-1451-2-ND"))
      (libsource (lib "eagle-import") (part "ek-tm4c129exl_C-USC0603K"))
    )
    (comp (ref "C19")
      (value "0.1uF")
      (footprint "eagle-import:C0402")
      (libsource (lib "eagle-import") (part "ek-tm4c129exl_C-USC0402"))
    )
    (comp (ref "C20")
      (value "2.2uF")
      (footprint "eagle-import:C0603K")
      (fields (field (name "DIGIKEY_PARTNUM") "311-1451-2-ND"))
      (libsource (lib "eagle-import") (part "ek-tm4c129exl_C-USC0603K"))
    )
    (comp (ref "C21")
      (value "0.1uF")
      (footprint "eagle-import:C0402")
      (libsource (lib "eagle-import") (part "ek-tm4c129exl_C-USC0402"))
    )
    (comp (ref "C40")
      (value "0.1uF")
      (footprint "eagle-import:C0402")
      (libsource (lib "eagle-import") (part "ek-tm4c129exl_C-USC0402"))
    )
    (comp (ref "C41")
      (value "0.1uF")
      (footprint "eagle-import:C0402")
      (libsource (lib "eagle-import") (part "ek-tm4c129exl_C-USC0402"))
    )
    (comp (ref "C42")
      (value "0.1uF")
      (footprint "eagle-import:C0402")
      (libsource (lib "eagle-import") (part "ek-tm4c129exl_C-USC0402"))
    )
    (comp (ref "C43")
      (value "0.1uF")
      (footprint "eagle-import:C0402")
      (libsource (lib "eagle-import") (part "ek-tm4c129exl_C-USC0402"))
    )
    (comp (ref "C44")
      (value "12pF")
      (footprint "eagle-import:C0402")
      (libsource (lib "eagle-import") (part "ek-tm4c129exl_C-USC0402"))
    )
    (comp (ref "C45")
      (value "12pF")
      (footprint "eagle-import:C0402")
      (libsource (lib "eagle-import") (part "ek-tm4c129exl_C-USC0402"))
    )
    (comp (ref "C46")
      (value "0.1uF")
      (footprint "eagle-import:C0402")
      (libsource (lib "eagle-import") (part "ek-tm4c129exl_C-USC0402"))
    )
    (comp (ref "C47")
      (value "12pF")
      (footprint "eagle-import:C0402")
      (libsource (lib "eagle-import") (part "ek-tm4c129exl_C-USC0402"))
    )
    (comp (ref "C48")
      (value "12pF")
      (footprint "eagle-import:C0402")
      (libsource (lib "eagle-import") (part "ek-tm4c129exl_C-USC0402"))
    )
    (comp (ref "D0")
      (value "LEDCHIPLED_0603")
      (footprint "eagle-import:CHIPLED_0603")
      (libsource (lib "eagle-import") (part "LEDCHIPLED_0603"))
    )
    (comp (ref "H1")
      (value "MOUNT-HOLE3.2")
      (footprint "eagle-import:3,2")
      (libsource (lib "eagle-import") (part "MOUNT-HOLE3.2"))
    )
    (comp (ref "H4")
      (value "MOUNT-HOLE3.2")
      (footprint "eagle-import:3,2")
      (libsource (lib "eagle-import") (part "MOUNT-HOLE3.2"))
    )
    (comp (ref "H6")
      (value "MOUNT-HOLE3.2")
      (footprint "eagle-import:3,2")
      (libsource (lib "eagle-import") (part "MOUNT-HOLE3.2"))
    )
    (comp (ref "J1")
      (value "JUMPER")
      (footprint "eagle-import:JUMP")
      (libsource (lib "eagle-import") (part "JUMPER"))
    )
    (comp (ref "J2")
      (value "JUMPER")
      (footprint "eagle-import:JUMP")
      (libsource (lib "eagle-import") (part "JUMPER"))
    )
    (comp (ref "J3")
      (value "JUMPER")
      (footprint "eagle-import:JUMP")
      (libsource (lib "eagle-import") (part "JUMPER"))
    )
    (comp (ref "JP1")
      (value "PINHD-2X3")
      (footprint "eagle-import:2X03")
      (libsource (lib "eagle-import") (part "PINHD-2X3"))
    )
    (comp (ref "JP2")
      (value "PINHD-1X2")
      (footprint "eagle-import:1X02")
      (libsource (lib "eagle-import") (part "PINHD-1X2"))
    )
    (comp (ref "JP3")
      (value "PINHD-1X2")
      (footprint "eagle-import:1X02")
      (libsource (lib "eagle-import") (part "PINHD-1X2"))
    )
    (comp (ref "R9")
      (value "330")
      (footprint "eagle-import:R0402")
      (libsource (lib "eagle-import") (part "ek-tm4c129exl_R-US_R0402"))
    )
    (comp (ref "R17")
      (value "100k")
      (footprint "eagle-import:R0402")
      (libsource (lib "eagle-import") (part "ek-tm4c129exl_R-US_R0402"))
    )
    (comp (ref "R25")
      (value "4.87k 1%")
      (footprint "eagle-import:R0402")
      (libsource (lib "eagle-import") (part "ek-tm4c129exl_R-US_R0402"))
    )
    (comp (ref "R26")
      (value "100k")
      (footprint "eagle-import:R0402")
      (libsource (lib "eagle-import") (part "ek-tm4c129exl_R-US_R0402"))
    )
    (comp (ref "R35")
      (value "10k")
      (footprint "eagle-import:R0402")
      (libsource (lib "eagle-import") (part "ek-tm4c129exl_R-US_R0402"))
    )
    (comp (ref "R36")
      (value "100k")
      (footprint "eagle-import:R0402")
      (libsource (lib "eagle-import") (part "ek-tm4c129exl_R-US_R0402"))
    )
    (comp (ref "R38")
      (value "51")
      (footprint "eagle-import:R0402")
      (libsource (lib "eagle-import") (part "ek-tm4c129exl_R-US_R0402"))
    )
    (comp (ref "R39")
      (value "0")
      (footprint "eagle-import:R0402")
      (libsource (lib "eagle-import") (part "ek-tm4c129exl_R-US_R0402"))
    )
    (comp (ref "R41")
      (value "0")
      (footprint "eagle-import:R0402")
      (libsource (lib "eagle-import") (part "ek-tm4c129exl_R-US_R0402"))
    )
    (comp (ref "R42")
      (value "1M")
      (footprint "eagle-import:R0402")
      (libsource (lib "eagle-import") (part "ek-tm4c129exl_R-US_R0402"))
    )
    (comp (ref "R44")
      (value "10k")
      (footprint "eagle-import:R0402")
      (libsource (lib "eagle-import") (part "ek-tm4c129exl_R-US_R0402"))
    )
    (comp (ref "R48")
      (value "R-US_R0402")
      (footprint "eagle-import:R0402")
      (fields (field (name "POPOP") "OMIT"))
      (libsource (lib "eagle-import") (part "ek-tm4c129exl_R-US_R0402"))
    )
    (comp (ref "R49")
      (value "2k")
      (footprint "eagle-import:R0402")
      (libsource (lib "eagle-import") (part "ek-tm4c129exl_R-US_R0402"))
    )
    (comp (ref "R51")
      (value "100")
      (footprint "eagle-import:R0402")
      (libsource (lib "eagle-import") (part "ek-tm4c129exl_R-US_R0402"))
    )
    (comp (ref "RESET")
      (value "SWITCH_TACTILE")
      (footprint "eagle-import:SWITCH_6MM_6MM_TE_CON_SMD")
      (libsource (lib "eagle-import") (part "SWITCH_TACTILE"))
    )
    (comp (ref "TP3")
      (value "TPPAD1-13")
      (footprint "eagle-import:P1-13")
      (libsource (lib "eagle-import") (part "TPPAD1-13"))
    )
    (comp (ref "TP8")
      (value "TPPAD1-13")
      (footprint "eagle-import:P1-13")
      (libsource (lib "eagle-import") (part "TPPAD1-13"))
    )
    (comp (ref "TP9")
      (value "TPPAD1-13")
      (footprint "eagle-import:P1-13")
      (libsource (lib "eagle-import") (part "TPPAD1-13"))
    )
    (comp (ref "TP10")
      (value "TPPAD1-13")
      (footprint "eagle-import:P1-13")
      (libsource (lib "eagle-import") (part "TPPAD1-13"))
    )
    (comp (ref "TP11")
      (value "TPPAD1-13")
      (footprint "eagle-import:P1-13")
      (libsource (lib "eagle-import") (part "TPPAD1-13"))
    )
    (comp (ref "TP12")
      (value "TPPAD1-13")
      (footprint "eagle-import:P1-13")
      (libsource (lib "eagle-import") (part "TPPAD1-13"))
    )
    (comp (ref "TP13")
      (value "TPPAD1-13")
      (footprint "eagle-import:P1-13")
      (libsource (lib "eagle-import") (part "TPPAD1-13"))
    )
    (comp (ref "U4")
      (value "TPS2052B_DRB_8")
      (footprint "eagle-import:DRB8_2P4X1P65")
      (fields
        (field (name "GENERIC_PART_NUMBER") "TPS2052B")
        (field (name "MANUFACTURER") "Texas Instruments")
        (field (name "MANUFACTURER_PART_NUMBER") "tps2052b_drb_8")
      )
      (libsource (lib "eagle-import") (part "TPS2052B_DRB_8"))
    )
    (comp (ref "U5")
      (value "TPS73733_DRV_6")
      (footprint "eagle-import:DRV6_1P6X1")
      (libsource (lib "eagle-import") (part "TPS73733_DRV_6"))
    )
    (comp (ref "WAKE")
      (value "SWITCH_TACTILE")
      (footprint "eagle-import:SWITCH_6MM_6MM_TE_CON_SMD")
      (libsource (lib "eagle-import") (part "SWITCH_TACTILE"))
    )
    (comp (ref "Y1")
      (value "25Mhz")
      (footprint "eagle-import:NDK3.2X2.5")
      (libsource (lib "eagle-import") (part "NX3225GA"))
    )
    (comp (ref "Y3")
      (value "CRYATL_32K_SMD")
      (footprint "eagle-import:CRYSTAL_32K_SMD")
      (libsource (lib "eagle-import") (part "CRYATL_32K_SMD"))
    )
  )
  (nets
    (net (code "1") (name "+3V3") (class "Default")
      (node (ref "C10") (pin "1") (pinfunction "1_1") (pintype "passive"))
      (node (ref "C11") (pin "1") (pinfunction "1_1") (pintype "passive"))
      (node (ref "C12") (pin "1") (pinfunction "1_1") (pintype "passive"))
      (node (ref "C13") (pin "1") (pinfunction "1_1") (pintype "passive"))
      (node (ref "C23") (pin "1") (pinfunction "1_1") (pintype "passive"))
      (node (ref "C25") (pin "1") (pinfunction "1_1") (pintype "passive"))
      (node (ref "C27") (pin "1") (pinfunction "1_1") (pintype "passive"))
      (node (ref "C29") (pin "1") (pinfunction "1_1") (pintype "passive"))
      (node (ref "D0") (pin "A") (pinfunction "A_A") (pintype "passive"))
      (node (ref "JP2") (pin "1") (pinfunction "1_1") (pintype "passive"))
      (node (ref "JP3") (pin "1") (pinfunction "1_1") (pintype "passive"))
      (node (ref "R3") (pin "2") (pinfunction "2_2") (pintype "passive"))
      (node (ref "R4") (pin "1") (pinfunction "1_1") (pintype "passive"))
      (node (ref "R5") (pin "1") (pinfunction "1_1") (pintype "passive"))
      (node (ref "U20") (pin "P$11") (pinfunction "VDD0_P$11") (pintype "bidirectional"))
      (node (ref "U20") (pin "P$2") (pinfunction "VDDA_P$2") (pintype "bidirectional"))
      (node (ref "U20") (pin "P$26") (pinfunction "VDD1_P$26") (pintype "bidirectional"))
      (node (ref "U20") (pin "P$37") (pinfunction "VBAT_P$37") (pintype "bidirectional"))
      (node (ref "U20") (pin "P$42") (pinfunction "VDD2_P$42") (pintype "bidirectional"))
      (node (ref "U20") (pin "P$54") (pinfunction "VDD3_P$54") (pintype "bidirectional"))
      (node (ref "U21") (pin "1") (pinfunction "VTREF_1") (pintype "bidirectional"))
      (node (ref "U6") (pin "P1") (pinfunction "VTARGET_P1") (pintype "bidirectional"))
      (node (ref "X11") (pin "1") (pinfunction "1_1") (pintype "passive"))
      (node (ref "X11") (pin "98") (pinfunction "1_98") (pintype "passive"))
      (node (ref "X6") (pin "1") (pinfunction "1_1") (pintype "passive"))
      (node (ref "X8") (pin "1") (pinfunction "1_1") (pintype "passive"))
    )
    (net (code "2") (name "+5V") (class "Default")
      (node (ref "C21") (pin "1") (pinfunction "1_1") (pintype "passive"))
      (node (ref "C24") (pin "1") (pinfunction "1_1") (pintype "passive"))
      (node (ref "C26") (pin "1") (pinfunction "1_1") (pintype "passive"))
      (node (ref "C28") (pin "1") (pinfunction "1_1") (pintype "passive"))
      (node (ref "C30") (pin "1") (pinfunction "1_1") (pintype "passive"))
      (node (ref "R17") (pin "1") (pinfunction "1_1") (pintype "passive"))
      (node (ref "U4") (pin "7") (pinfunction "OUT1_7") (pintype "output"))
      (node (ref "U5") (pin "6") (pinfunction "IN_6") (pintype "input"))
      (node (ref "X11") (pin "2") (pinfunction "1_2") (pintype "passive"))
      (node (ref "X11") (pin "97") (pinfunction "1_97") (pintype "passive"))
      (node (ref "X6") (pin "2") (pinfunction "1_2") (pintype "passive"))
      (node (ref "X8") (pin "2") (pinfunction "1_2") (pintype "passive"))
    )
    (net (code "4") (name "BP2_A2.5") (class "Default")
      (node (ref "JP4") (pin "4") (pinfunction "4_4") (pintype "passive"))
      (node (ref "X6") (pin "9") (pinfunction "1_9") (pintype "passive"))
    )
    (net (code "5") (name "BP2_A2.6") (class "Default")
      (node (ref "JP5") (pin "4") (pinfunction "4_4") (pintype "passive"))
      (node (ref "X6") (pin "11") (pinfunction "1_11") (pintype "passive"))
    )
    (net (code "6") (name "DEBUG_ACTIVE") (class "Default")
      (node (ref "TP1") (pin "TP") (pinfunction "TP_TP") (pintype "input"))
      (node (ref "U20") (pin "P$64") (pinfunction "PD3_P$64") (pintype "bidirectional"))
    )
    (net (code "7") (name "DEBUG_PC0{slash}TCK{slash}SWCLK") (class "Default")
      (node (ref "R8") (pin "2") (pinfunction "2_2") (pintype "passive"))
      (node (ref "U20") (pin "P$19") (pinfunction "PA2_P$19") (pintype "bidirectional"))
      (node (ref "U20") (pin "P$30") (pinfunction "PF2_P$30") (pintype "bidirectional"))
      (node (ref "U6") (pin "P4") (pinfunction "TCK_P4") (pintype "bidirectional"))
      (node (ref "X1") (pin "9") (pinfunction "1_9") (pintype "passive"))
    )
    (net (code "8") (name "DEBUG_PC1{slash}TMS{slash}SWDIO") (class "Default")
      (node (ref "R10") (pin "2") (pinfunction "2_2") (pintype "passive"))
      (node (ref "U20") (pin "P$20") (pinfunction "PA3_P$20") (pintype "bidirectional"))
      (node (ref "U20") (pin "P$29") (pinfunction "PF1_P$29") (pintype "bidirectional"))
      (node (ref "U6") (pin "P2") (pinfunction "TMS_P2") (pintype "bidirectional"))
      (node (ref "X1") (pin "7") (pinfunction "1_7") (pintype "passive"))
    )
    (net (code "9") (name "DEBUG_PC2{slash}TDI") (class "Default")
      (node (ref "R11") (pin "2") (pinfunction "2_2") (pintype "passive"))
      (node (ref "U20") (pin "P$22") (pinfunction "PA5_P$22") (pintype "bidirectional"))
      (node (ref "U6") (pin "P8") (pinfunction "TDI_P8") (pintype "bidirectional"))
      (node (ref "X1") (pin "5") (pinfunction "1_5") (pintype "passive"))
    )
    (net (code "10") (name "DEBUG_PC3{slash}TDO{slash}SWO") (class "Default")
      (node (ref "R15") (pin "2") (pinfunction "2_2") (pintype "passive"))
      (node (ref "U20") (pin "P$21") (pinfunction "PA4_P$21") (pintype "bidirectional"))
      (node (ref "U20") (pin "P$53") (pinfunction "PD6_P$53") (pintype "bidirectional"))
      (node (ref "U6") (pin "P6") (pinfunction "TDO_P6") (pintype "bidirectional"))
      (node (ref "X1") (pin "3") (pinfunction "1_3") (pintype "passive"))
    )
    (net (code "11") (name "DEBUG_VBUS") (class "Default")
      (node (ref "JP1") (pin "5") (pinfunction "5_5") (pintype "passive"))
      (node (ref "R28") (pin "2") (pinfunction "2_2") (pintype "passive"))
      (node (ref "U22") (pin "P1") (pinfunction "VBUS_P1") (pintype "bidirectional"))
      (node (ref "U3") (pin "6") (pinfunction "VBUS_6") (pintype "passive"))
    )
    (net (code "12") (name "EN0RXI_N") (class "Default")
      (node (ref "R21") (pin "2") (pinfunction "2_2") (pintype "passive"))
      (node (ref "U1") (pin "P$53") (pinfunction "EN0RXIN_P$53") (pintype "bidirectional"))
      (node (ref "U10") (pin "P$8") (pinfunction "P$8_P$8") (pintype "bidirectional"))
    )
    (net (code "13") (name "EN0RXI_P") (class "Default")
      (node (ref "R22") (pin "2") (pinfunction "2_2") (pintype "passive"))
      (node (ref "U1") (pin "P$54") (pinfunction "EN0RXIP_P$54") (pintype "bidirectional"))
      (node (ref "U10") (pin "P$6") (pinfunction "P$6_P$6") (pintype "bidirectional"))
    )
    (net (code "14") (name "EN0TXO_N") (class "Default")
      (node (ref "R23") (pin "2") (pinfunction "2_2") (pintype "passive"))
      (node (ref "U1") (pin "P$56") (pinfunction "EN0TXON_P$56") (pintype "bidirectional"))
      (node (ref "U10") (pin "P$3") (pinfunction "P$3_P$3") (pintype "bidirectional"))
    )
    (net (code "15") (name "EN0TXO_P") (class "Default")
      (node (ref "R24") (pin "2") (pinfunction "2_2") (pintype "passive"))
      (node (ref "U1") (pin "P$57") (pinfunction "EN0TXOP_P$57") (pintype "bidirectional"))
      (node (ref "U10") (pin "P$1") (pinfunction "P$1_P$1") (pintype "bidirectional"))
    )
    (net (code "16") (name "GND") (class "Default")
      (node (ref "C10") (pin "2") (pinfunction "2_2") (pintype "passive"))
      (node (ref "C11") (pin "2") (pinfunction "2_2") (pintype "passive"))
      (node (ref "C12") (pin "2") (pinfunction "2_2") (pintype "passive"))
      (node (ref "C13") (pin "2") (pinfunction "2_2") (pintype "passive"))
      (node (ref "C14") (pin "2") (pinfunction "2_2") (pintype "passive"))
      (node (ref "C15") (pin "2") (pinfunction "2_2") (pintype "passive"))
      (node (ref "C16") (pin "2") (pinfunction "2_2") (pintype "passive"))
      (node (ref "C17") (pin "2") (pinfunction "2_2") (pintype "passive"))
      (node (ref "C18") (pin "2") (pinfunction "2_2") (pintype "passive"))
      (node (ref "C19") (pin "2") (pinfunction "2_2") (pintype "passive"))
      (node (ref "C2") (pin "2") (pinfunction "2_2") (pintype "passive"))
      (node (ref "C20") (pin "2") (pinfunction "2_2") (pintype "passive"))
      (node (ref "C21") (pin "2") (pinfunction "2_2") (pintype "passive"))
      (node (ref "C22") (pin "2") (pinfunction "2_2") (pintype "passive"))
      (node (ref "C23") (pin "2") (pinfunction "2_2") (pintype "passive"))
      (node (ref "C24") (pin "2") (pinfunction "2_2") (pintype "passive"))
      (node (ref "C25") (pin "2") (pinfunction "2_2") (pintype "passive"))
      (node (ref "C26") (pin "2") (pinfunction "2_2") (pintype "passive"))
      (node (ref "C27") (pin "2") (pinfunction "2_2") (pintype "passive"))
      (node (ref "C28") (pin "2") (pinfunction "2_2") (pintype "passive"))
      (node (ref "C29") (pin "2") (pinfunction "2_2") (pintype "passive"))
      (node (ref "C3") (pin "2") (pinfunction "2_2") (pintype "passive"))
      (node (ref "C30") (pin "2") (pinfunction "2_2") (pintype "passive"))
      (node (ref "C31") (pin "2") (pinfunction "2_2") (pintype "passive"))
      (node (ref "C32") (pin "2") (pinfunction "2_2") (pintype "passive"))
      (node (ref "C33") (pin "2") (pinfunction "2_2") (pintype "passive"))
      (node (ref "C4") (pin "2") (pinfunction "2_2") (pintype "passive"))
      (node (ref "C40") (pin "2") (pinfunction "2_2") (pintype "passive"))
      (node (ref "C41") (pin "2") (pinfunction "2_2") (pintype "passive"))
      (node (ref "C42") (pin "2") (pinfunction "2_2") (pintype "passive"))
      (node (ref "C43") (pin "2") (pinfunction "2_2") (pintype "passive"))
      (node (ref "C44") (pin "2") (pinfunction "2_2") (pintype "passive"))
      (node (ref "C45") (pin "2") (pinfunction "2_2") (pintype "passive"))
      (node (ref "C46") (pin "2") (pinfunction "2_2") (pintype "passive"))
      (node (ref "C47") (pin "2") (pinfunction "2_2") (pintype "passive"))
      (node (ref "C48") (pin "2") (pinfunction "2_2") (pintype "passive"))
      (node (ref "C5") (pin "2") (pinfunction "2_2") (pintype "passive"))
      (node (ref "C6") (pin "2") (pinfunction "2_2") (pintype "passive"))
      (node (ref "C7") (pin "2") (pinfunction "2_2") (pintype "passive"))
      (node (ref "C8") (pin "2") (pinfunction "2_2") (pintype "passive"))
      (node (ref "C9") (pin "2") (pinfunction "2_2") (pintype "passive"))
      (node (ref "R12") (pin "2") (pinfunction "2_2") (pintype "passive"))
      (node (ref "R13") (pin "2") (pinfunction "2_2") (pintype "passive"))
      (node (ref "R14") (pin "2") (pinfunction "2_2") (pintype "passive"))
      (node (ref "R25") (pin "2") (pinfunction "2_2") (pintype "passive"))
      (node (ref "R26") (pin "2") (pinfunction "2_2") (pintype "passive"))
      (node (ref "R27") (pin "1") (pinfunction "1_1") (pintype "passive"))
      (node (ref "R29") (pin "1") (pinfunction "1_1") (pintype "passive"))
      (node (ref "R30") (pin "1") (pinfunction "1_1") (pintype "passive"))
      (node (ref "R31") (pin "1") (pinfunction "1_1") (pintype "passive"))
      (node (ref "R33") (pin "1") (pinfunction "1_1") (pintype "passive"))
      (node (ref "R34") (pin "1") (pinfunction "1_1") (pintype "passive"))
      (node (ref "R47") (pin "1") (pinfunction "1_1") (pintype "passive"))
      (node (ref "R52") (pin "1") (pinfunction "1_1") (pintype "passive"))
      (node (ref "R9") (pin "1") (pinfunction "1_1") (pintype "passive"))
      (node (ref "RESET") (pin "P$1") (pinfunction "0_P$1") (pintype "passive"))
      (node (ref "RESET") (pin "P$2") (pinfunction "0_P$2") (pintype "passive"))
      (node (ref "TP14") (pin "TP") (pinfunction "TP_TP") (pintype "input"))
      (node (ref "TP15") (pin "TP") (pinfunction "TP_TP") (pintype "input"))
      (node (ref "TP16") (pin "TP") (pinfunction "TP_TP") (pintype "input"))
      (node (ref "TP17") (pin "TP") (pinfunction "TP_TP") (pintype "input"))
      (node (ref "U1") (pin "P$10") (pinfunction "GNDA_P$10") (pintype "bidirectional"))
      (node (ref "U1") (pin "P$114") (pinfunction "GND_P$114") (pintype "bidirectional"))
      (node (ref "U1") (pin "P$17") (pinfunction "GND_P$17") (pintype "bidirectional"))
      (node (ref "U1") (pin "P$48") (pinfunction "GND_P$48") (pintype "bidirectional"))
      (node (ref "U1") (pin "P$55") (pinfunction "GND_P$55") (pintype "bidirectional"))
      (node (ref "U1") (pin "P$58") (pinfunction "GND_P$58") (pintype "bidirectional"))
      (node (ref "U1") (pin "P$80") (pinfunction "GND_P$80") (pintype "bidirectional"))
      (node (ref "U2") (pin "4") (pinfunction "GND_4") (pintype "power_in"))
      (node (ref "U20") (pin "P$12") (pinfunction "GND0_P$12") (pintype "bidirectional"))
      (node (ref "U20") (pin "P$27") (pinfunction "GND1_P$27") (pintype "bidirectional"))
      (node (ref "U20") (pin "P$3") (pinfunction "GNDA_P$3") (pintype "bidirectional"))
      (node (ref "U20") (pin "P$32") (pinfunction "~{WAKE}_P$32") (pintype "bidirectional"))
      (node (ref "U20") (pin "P$34") (pinfunction "XOSC0_P$34") (pintype "bidirectional"))
      (node (ref "U20") (pin "P$35") (pinfunction "GNDX_P$35") (pintype "bidirectional"))
      (node (ref "U20") (pin "P$39") (pinfunction "GND2_P$39") (pintype "bidirectional"))
      (node (ref "U20") (pin "P$55") (pinfunction "GND3_P$55") (pintype "bidirectional"))
      (node (ref "U21") (pin "3") (pinfunction "GND_3") (pintype "bidirectional"))
      (node (ref "U21") (pin "5") (pinfunction "NC_5") (pintype "bidirectional"))
      (node (ref "U21") (pin "9") (pinfunction "~{TRST}_9") (pintype "bidirectional"))
      (node (ref "U22") (pin "P5") (pinfunction "GND_P5") (pintype "bidirectional"))
      (node (ref "U3") (pin "4") (pinfunction "GND_4") (pintype "power_in"))
      (node (ref "U4") (pin "1") (pinfunction "GND_1") (pintype "power_in"))
      (node (ref "U4") (pin "9") (pinfunction "EPAD_9") (pintype "passive"))
      (node (ref "U4") (pin "V") (pinfunction "VIA_V") (pintype "bidirectional"))
      (node (ref "U4") (pin "V_2") (pinfunction "VIA_V_2") (pintype "bidirectional"))
      (node (ref "U4") (pin "V_3") (pinfunction "VIA_V_3") (pintype "bidirectional"))
      (node (ref "U4") (pin "V_4") (pinfunction "VIA_V_4") (pintype "bidirectional"))
      (node (ref "U4") (pin "V_5") (pinfunction "VIA_V_5") (pintype "bidirectional"))
      (node (ref "U4") (pin "V_6") (pinfunction "VIA_V_6") (pintype "bidirectional"))
      (node (ref "U5") (pin "3") (pinfunction "GND_3") (pintype "power_in"))
      (node (ref "U5") (pin "7") (pinfunction "EPAD_7") (pintype "passive"))
      (node (ref "U5") (pin "V") (pinfunction "VIA_V") (pintype "bidirectional"))
      (node (ref "U5") (pin "V_2") (pinfunction "VIA_V_2") (pintype "bidirectional"))
      (node (ref "U6") (pin "P5") (pinfunction "GND_P5") (pintype "bidirectional"))
      (node (ref "U6") (pin "P9") (pinfunction "GND1_P9") (pintype "bidirectional"))
      (node (ref "U7") (pin "P5") (pinfunction "GND_P5") (pintype "bidirectional"))
      (node (ref "USR_SW1") (pin "P$3") (pinfunction "1_P$3") (pintype "passive"))
      (node (ref "USR_SW1") (pin "P$4") (pinfunction "1_P$4") (pintype "passive"))
      (node (ref "USR_SW2") (pin "P$3") (pinfunction "1_P$3") (pintype "passive"))
      (node (ref "USR_SW2") (pin "P$4") (pinfunction "1_P$4") (pintype "passive"))
      (node (ref "WAKE") (pin "P$3") (pinfunction "1_P$3") (pintype "passive"))
      (node (ref "WAKE") (pin "P$4") (pinfunction "1_P$4") (pintype "passive"))
      (node (ref "X11") (pin "3") (pinfunction "1_3") (pintype "passive"))
      (node (ref "X11") (pin "35") (pinfunction "1_35") (pintype "passive"))
      (node (ref "X11") (pin "36") (pinfunction "1_36") (pintype "passive"))
      (node (ref "X11") (pin "4") (pinfunction "1_4") (pintype "passive"))
      (node (ref "X11") (pin "61") (pinfunction "1_61") (pintype "passive"))
      (node (ref "X11") (pin "62") (pinfunction "1_62") (pintype "passive"))
      (node (ref "X11") (pin "96") (pinfunction "1_96") (pintype "passive"))
      (node (ref "X6") (pin "4") (pinfunction "1_4") (pintype "passive"))
      (node (ref "X7") (pin "2") (pinfunction "1_2") (pintype "passive"))
      (node (ref "X8") (pin "4") (pinfunction "1_4") (pintype "passive"))
      (node (ref "X9") (pin "2") (pinfunction "1_2") (pintype "passive"))
    )
    (net (code "17") (name "ICDI_RESET") (class "Default")
      (node (ref "C2") (pin "1") (pinfunction "1_1") (pintype "passive"))
      (node (ref "R3") (pin "1") (pinfunction "1_1") (pintype "passive"))
      (node (ref "U20") (pin "P$38") (pinfunction "~{RESET}_P$38") (pintype "bidirectional"))
      (node (ref "U21") (pin "10") (pinfunction "RESET_10") (pintype "bidirectional"))
    )
    (net (code "18") (name "ICDI_TCK") (class "Default")
      (node (ref "R4") (pin "2") (pinfunction "2_2") (pintype "passive"))
      (node (ref "U20") (pin "P$52") (pinfunction "PC0/TCK_P$52") (pintype "bidirectional"))
      (node (ref "U21") (pin "4") (pinfunction "TCK_4") (pintype "bidirectional"))
    )
    (net (code "19") (name "ICDI_TDI") (class "Default")
      (node (ref "U20") (pin "P$50") (pinfunction "PC2/TDI_P$50") (pintype "bidirectional"))
      (node (ref "U21") (pin "8") (pinfunction "TDI_8") (pintype "bidirectional"))
    )
    (net (code "20") (name "ICDI_TDO") (class "Default")
      (node (ref "U20") (pin "P$49") (pinfunction "PC3/TDO_P$49") (pintype "bidirectional"))
      (node (ref "U21") (pin "6") (pinfunction "TDO_6") (pintype "bidirectional"))
    )
    (net (code "21") (name "ICDI_TMS") (class "Default")
      (node (ref "R5") (pin "2") (pinfunction "2_2") (pintype "passive"))
      (node (ref "U20") (pin "P$51") (pinfunction "PC1/TMS_P$51") (pintype "bidirectional"))
      (node (ref "U21") (pin "2") (pinfunction "TMS_2") (pintype "bidirectional"))
    )
    (net (code "22") (name "ICDI_USBD_N") (class "Default")
      (node (ref "U20") (pin "P$43") (pinfunction "PD4_P$43") (pintype "bidirectional"))
      (node (ref "U22") (pin "P2") (pinfunction "DM_P2") (pintype "bidirectional"))
      (node (ref "U3") (pin "2") (pinfunction "D-_2") (pintype "passive"))
    )
    (net (code "23") (name "ICDI_USBD_P") (class "Default")
      (node (ref "U20") (pin "P$44") (pinfunction "PD5_P$44") (pintype "bidirectional"))
      (node (ref "U22") (pin "P3") (pinfunction "DP_P3") (pintype "bidirectional"))
      (node (ref "U3") (pin "1") (pinfunction "D+_1") (pintype "passive"))
    )
    (net (code "24") (name "ICDI_VDDC") (class "Default")
      (node (ref "C5") (pin "1") (pinfunction "1_1") (pintype "passive"))
      (node (ref "C6") (pin "1") (pinfunction "1_1") (pintype "passive"))
      (node (ref "C7") (pin "1") (pinfunction "1_1") (pintype "passive"))
      (node (ref "U20") (pin "P$25") (pinfunction "VDDC0_P$25") (pintype "bidirectional"))
      (node (ref "U20") (pin "P$56") (pinfunction "VDDC1_P$56") (pintype "bidirectional"))
    )
    (net (code "25") (name "MCU_3V3") (class "Default")
      (node (ref "C16") (pin "1") (pinfunction "1_1") (pintype "passive"))
      (node (ref "C17") (pin "1") (pinfunction "1_1") (pintype "passive"))
      (node (ref "C18") (pin "1") (pinfunction "1_1") (pintype "passive"))
      (node (ref "C22") (pin "1") (pinfunction "1_1") (pintype "passive"))
      (node (ref "C40") (pin "1") (pinfunction "1_1") (pintype "passive"))
      (node (ref "C41") (pin "1") (pinfunction "1_1") (pintype "passive"))
      (node (ref "C42") (pin "1") (pinfunction "1_1") (pintype "passive"))
      (node (ref "C43") (pin "1") (pinfunction "1_1") (pintype "passive"))
      (node (ref "JP2") (pin "2") (pinfunction "2_2") (pintype "passive"))
      (node (ref "R1") (pin "1") (pinfunction "1_1") (pintype "passive"))
      (node (ref "R2") (pin "1") (pinfunction "1_1") (pintype "passive"))
      (node (ref "R21") (pin "1") (pinfunction "1_1") (pintype "passive"))
      (node (ref "R22") (pin "1") (pinfunction "1_1") (pintype "passive"))
      (node (ref "R23") (pin "1") (pinfunction "1_1") (pintype "passive"))
      (node (ref "R24") (pin "1") (pinfunction "1_1") (pintype "passive"))
      (node (ref "R39") (pin "2") (pinfunction "2_2") (pintype "passive"))
      (node (ref "R41") (pin "2") (pinfunction "2_2") (pintype "passive"))
      (node (ref "R44") (pin "1") (pinfunction "1_1") (pintype "passive"))
      (node (ref "U1") (pin "P$101") (pinfunction "VDD_P$101") (pintype "bidirectional"))
      (node (ref "U1") (pin "P$113") (pinfunction "VDD_P$113") (pintype "bidirectional"))
      (node (ref "U1") (pin "P$122") (pinfunction "VDD_P$122") (pintype "bidirectional"))
      (node (ref "U1") (pin "P$16") (pinfunction "VDD_P$16") (pintype "bidirectional"))
      (node (ref "U1") (pin "P$26") (pinfunction "VDD_P$26") (pintype "bidirectional"))
      (node (ref "U1") (pin "P$28") (pinfunction "VDD_P$28") (pintype "bidirectional"))
      (node (ref "U1") (pin "P$39") (pinfunction "VDD_P$39") (pintype "bidirectional"))
      (node (ref "U1") (pin "P$47") (pinfunction "VDD_P$47") (pintype "bidirectional"))
      (node (ref "U1") (pin "P$51") (pinfunction "VDD_P$51") (pintype "bidirectional"))
      (node (ref "U1") (pin "P$52") (pinfunction "VDD_P$52") (pintype "bidirectional"))
      (node (ref "U1") (pin "P$69") (pinfunction "VDD_P$69") (pintype "bidirectional"))
      (node (ref "U1") (pin "P$7") (pinfunction "VDD_P$7") (pintype "bidirectional"))
      (node (ref "U1") (pin "P$79") (pinfunction "VDD_P$79") (pintype "bidirectional"))
      (node (ref "U1") (pin "P$8") (pinfunction "VDDA_P$8") (pintype "bidirectional"))
      (node (ref "U1") (pin "P$90") (pinfunction "VDD_P$90") (pintype "bidirectional"))
      (node (ref "U10") (pin "P$2") (pinfunction "P$2_P$2") (pintype "bidirectional"))
      (node (ref "U10") (pin "P$7") (pinfunction "P$7_P$7") (pintype "bidirectional"))
    )
    (net (code "26") (name "Net-(C1-Pad1)") (class "Default")
      (node (ref "C1") (pin "1") (pinfunction "1_1") (pintype "passive"))
      (node (ref "R32") (pin "1") (pinfunction "1_1") (pintype "passive"))
      (node (ref "R43") (pin "1") (pinfunction "1_1") (pintype "passive"))
      (node (ref "R45") (pin "1") (pinfunction "1_1") (pintype "passive"))
      (node (ref "R46") (pin "1") (pinfunction "1_1") (pintype "passive"))
    )
    (net (code "27") (name "Net-(C1-Pad2)") (class "Default")
      (node (ref "C1") (pin "2") (pinfunction "2_2") (pintype "passive"))
      (node (ref "C31") (pin "1") (pinfunction "1_1") (pintype "passive"))
      (node (ref "R47") (pin "2") (pinfunction "2_2") (pintype "passive"))
      (node (ref "U14") (pin "10") (pinfunction "CHASSIS_10") (pintype "bidirectional"))
      (node (ref "U14") (pin "9") (pinfunction "CHASSIS_9") (pintype "bidirectional"))
    )
    (net (code "28") (name "Net-(C14-Pad1)") (class "Default")
      (node (ref "C14") (pin "1") (pinfunction "1_1") (pintype "passive"))
      (node (ref "C15") (pin "1") (pinfunction "1_1") (pintype "passive"))
      (node (ref "C4") (pin "1") (pinfunction "1_1") (pintype "passive"))
      (node (ref "TP12") (pin "TP") (pinfunction "TP_TP") (pintype "input"))
      (node (ref "U1") (pin "P$115") (pinfunction "VDDC_P$115") (pintype "bidirectional"))
      (node (ref "U1") (pin "P$87") (pinfunction "VDDC_P$87") (pintype "bidirectional"))
    )
    (net (code "29") (name "Net-(D0-PadC)") (class "Default")
      (node (ref "D0") (pin "C") (pinfunction "C_C") (pintype "passive"))
      (node (ref "R9") (pin "2") (pinfunction "2_2") (pintype "passive"))
    )
    (net (code "30") (name "Net-(D1-PadC)") (class "Default")
      (node (ref "D1") (pin "C") (pinfunction "C_C") (pintype "passive"))
      (node (ref "R33") (pin "2") (pinfunction "2_2") (pintype "passive"))
    )
    (net (code "31") (name "Net-(D2-PadC)") (class "Default")
      (node (ref "D2") (pin "C") (pinfunction "C_C") (pintype "passive"))
      (node (ref "R27") (pin "2") (pinfunction "2_2") (pintype "passive"))
    )
    (net (code "32") (name "Net-(D3-PadC)") (class "Default")
      (node (ref "D3") (pin "C") (pinfunction "C_C") (pintype "passive"))
      (node (ref "R31") (pin "2") (pinfunction "2_2") (pintype "passive"))
    )
    (net (code "33") (name "Net-(D4-PadC)") (class "Default")
      (node (ref "D4") (pin "C") (pinfunction "C_C") (pintype "passive"))
      (node (ref "R30") (pin "2") (pinfunction "2_2") (pintype "passive"))
    )
    (net (code "34") (name "Net-(R32-Pad2)") (class "Default")
      (node (ref "R32") (pin "2") (pinfunction "2_2") (pintype "passive"))
      (node (ref "U10") (pin "P$15") (pinfunction "P$15_P$15") (pintype "bidirectional"))
    )
    (net (code "35") (name "Net-(R38-Pad1)") (class "Default")
      (node (ref "R38") (pin "1") (pinfunction "1_1") (pintype "passive"))
      (node (ref "R39") (pin "1") (pinfunction "1_1") (pintype "passive"))
      (node (ref "R42") (pin "1") (pinfunction "1_1") (pintype "passive"))
      (node (ref "TP11") (pin "TP") (pinfunction "TP_TP") (pintype "input"))
    )
    (net (code "36") (name "Net-(R43-Pad2)") (class "Default")
      (node (ref "R43") (pin "2") (pinfunction "2_2") (pintype "passive"))
      (node (ref "U10") (pin "P$10") (pinfunction "P$10_P$10") (pintype "bidirectional"))
    )
    (net (code "37") (name "Net-(U1B-OSC0)") (class "Default")
      (node (ref "C44") (pin "1") (pinfunction "1_1") (pintype "passive"))
      (node (ref "U1") (pin "P$88") (pinfunction "OSC0_P$88") (pintype "bidirectional"))
      (node (ref "Y1") (pin "P$3") (pinfunction "OSC1_P$3") (pintype "bidirectional"))
    )
    (net (code "38") (name "Net-(U1B-OSC1)") (class "Default")
      (node (ref "R49") (pin "2") (pinfunction "2_2") (pintype "passive"))
      (node (ref "U1") (pin "P$89") (pinfunction "OSC1_P$89") (pintype "bidirectional"))
    )
    (net (code "39") (name "Net-(U1B-VBAT)") (class "Default")
      (node (ref "C3") (pin "1") (pinfunction "1_1") (pintype "passive"))
      (node (ref "R38") (pin "2") (pinfunction "2_2") (pintype "passive"))
      (node (ref "U1") (pin "P$68") (pinfunction "VBAT_P$68") (pintype "bidirectional"))
    )
    (net (code "40") (name "Net-(U1B-XOSC0)") (class "Default")
      (node (ref "C48") (pin "1") (pinfunction "1_1") (pintype "passive"))
      (node (ref "U1") (pin "P$66") (pinfunction "XOSC0_P$66") (pintype "bidirectional"))
      (node (ref "Y3") (pin "P$1") (pinfunction "P$1_P$1") (pintype "bidirectional"))
    )
    (net (code "41") (name "Net-(U1B-XOSC1)") (class "Default")
      (node (ref "C47") (pin "1") (pinfunction "1_1") (pintype "passive"))
      (node (ref "U1") (pin "P$67") (pinfunction "XOSC1_P$67") (pintype "bidirectional"))
      (node (ref "Y3") (pin "P$2") (pinfunction "P$2_P$2") (pintype "bidirectional"))
    )
    (net (code "42") (name "Net-(U1B-~{HIB})") (class "Default")
      (node (ref "TP9") (pin "TP") (pinfunction "TP_TP") (pintype "input"))
      (node (ref "U1") (pin "P$65") (pinfunction "~{HIB}_P$65") (pintype "bidirectional"))
    )
    (net (code "43") (name "Net-(U1B-~{RESET})") (class "Default")
      (node (ref "C46") (pin "1") (pinfunction "1_1") (pintype "passive"))
      (node (ref "R44") (pin "2") (pinfunction "2_2") (pintype "passive"))
      (node (ref "R51") (pin "2") (pinfunction "2_2") (pintype "passive"))
      (node (ref "U1") (pin "P$70") (pinfunction "~{RESET}_P$70") (pintype "bidirectional"))
    )
    (net (code "44") (name "Net-(U4-*EN1)") (class "Default")
      (node (ref "R26") (pin "1") (pinfunction "1_1") (pintype "passive"))
      (node (ref "R35") (pin "2") (pinfunction "2_2") (pintype "passive"))
      (node (ref "U4") (pin "3") (pinfunction "*EN1_3") (pintype "input"))
    )
    (net (code "45") (name "Net-(U4-*OC1)") (class "Default")
      (node (ref "R36") (pin "1") (pinfunction "1_1") (pintype "passive"))
      (node (ref "TP8") (pin "TP") (pinfunction "TP_TP") (pintype "input"))
      (node (ref "U4") (pin "8") (pinfunction "*OC1_8") (pintype "output"))
    )
    (net (code "46") (name "Net-(U5-EN)") (class "Default")
      (node (ref "R17") (pin "2") (pinfunction "2_2") (pintype "passive"))
      (node (ref "TP3") (pin "TP") (pinfunction "TP_TP") (pintype "input"))
      (node (ref "U5") (pin "4") (pinfunction "EN_4") (pintype "passive"))
    )
    (net (code "47") (name "Net-(U5-NR{slash}FB)") (class "Default")
      (node (ref "C19") (pin "1") (pinfunction "1_1") (pintype "passive"))
      (node (ref "R48") (pin "1") (pinfunction "1_1") (pintype "passive"))
      (node (ref "U5") (pin "2") (pinfunction "NR/FB_2") (pintype "bidirectional"))
    )
    (net (code "48") (name "Net-(U5-OUT)") (class "Default")
      (node (ref "C20") (pin "1") (pinfunction "1_1") (pintype "passive"))
      (node (ref "JP3") (pin "2") (pinfunction "2_2") (pintype "passive"))
      (node (ref "R48") (pin "2") (pinfunction "2_2") (pintype "passive"))
      (node (ref "U5") (pin "1") (pinfunction "OUT_1") (pintype "output"))
    )
    (net (code "49") (name "Net-(U6-~{EXTDBG})") (class "Default")
      (node (ref "R40") (pin "2") (pinfunction "2_2") (pintype "passive"))
      (node (ref "U6") (pin "P3") (pinfunction "~{EXTDBG}_P3") (pintype "bidirectional"))
    )
    (net (code "50") (name "Net-(U7B-S1)") (class "Default")
      (node (ref "C32") (pin "1") (pinfunction "1_1") (pintype "passive"))
      (node (ref "R52") (pin "2") (pinfunction "2_2") (pintype "passive"))
      (node (ref "U7") (pin "P$1") (pinfunction "S1_P$1") (pintype "passive"))
      (node (ref "U7") (pin "P$2") (pinfunction "S2_P$2") (pintype "passive"))
      (node (ref "U7") (pin "P$3") (pinfunction "S3_P$3") (pintype "passive"))
      (node (ref "U7") (pin "P$4") (pinfunction "S4_P$4") (pintype "passive"))
      (node (ref "U7") (pin "P$5") (pinfunction "S5_P$5") (pintype "passive"))
      (node (ref "U7") (pin "P$6") (pinfunction "S6_P$6") (pintype "passive"))
    )
    (net (code "51") (name "Net-(U13-P$1)") (class "Default")
      (node (ref "U10") (pin "P$16") (pinfunction "P$16_P$16") (pintype "bidirectional"))
      (node (ref "U13") (pin "1") (pinfunction "P$1_1") (pintype "bidirectional"))
      (node (ref "U13") (pin "8") (pinfunction "P$8_8") (pintype "bidirectional"))
      (node (ref "U14") (pin "1") (pinfunction "TX+_1") (pintype "bidirectional"))
    )
    (net (code "52") (name "Net-(U13-P$2)") (class "Default")
      (node (ref "U10") (pin "P$14") (pinfunction "P$14_P$14") (pintype "bidirectional"))
      (node (ref "U13") (pin "2") (pinfunction "P$2_2") (pintype "bidirectional"))
      (node (ref "U13") (pin "7") (pinfunction "P$7_7") (pintype "bidirectional"))
      (node (ref "U14") (pin "2") (pinfunction "TX-_2") (pintype "bidirectional"))
    )
    (net (code "53") (name "Net-(U13-P$3)") (class "Default")
      (node (ref "U10") (pin "P$11") (pinfunction "P$11_P$11") (pintype "bidirectional"))
      (node (ref "U13") (pin "3") (pinfunction "P$3_3") (pintype "bidirectional"))
      (node (ref "U13") (pin "6") (pinfunction "P$6_6") (pintype "bidirectional"))
      (node (ref "U14") (pin "3") (pinfunction "RX+_3") (pintype "bidirectional"))
    )
    (net (code "54") (name "Net-(U13-P$4)") (class "Default")
      (node (ref "U10") (pin "P$9") (pinfunction "P$9_P$9") (pintype "bidirectional"))
      (node (ref "U13") (pin "4") (pinfunction "P$4_4") (pintype "bidirectional"))
      (node (ref "U13") (pin "5") (pinfunction "P$5_5") (pintype "bidirectional"))
      (node (ref "U14") (pin "6") (pinfunction "RX-_6") (pintype "bidirectional"))
    )
    (net (code "55") (name "Net-(U14-TERM1A)") (class "Default")
      (node (ref "R45") (pin "2") (pinfunction "2_2") (pintype "passive"))
      (node (ref "U14") (pin "4") (pinfunction "TERM1A_4") (pintype "bidirectional"))
      (node (ref "U14") (pin "5") (pinfunction "TERM1B_5") (pintype "bidirectional"))
    )
    (net (code "56") (name "Net-(U14-TERM2A)") (class "Default")
      (node (ref "R46") (pin "2") (pinfunction "2_2") (pintype "passive"))
      (node (ref "U14") (pin "7") (pinfunction "TERM2A_7") (pintype "bidirectional"))
      (node (ref "U14") (pin "8") (pinfunction "TERM2B_8") (pintype "bidirectional"))
    )
    (net (code "57") (name "Net-(U20-OSC0)") (class "Default")
      (node (ref "C9") (pin "1") (pinfunction "1_1") (pintype "passive"))
      (node (ref "U20") (pin "P$40") (pinfunction "OSC0_P$40") (pintype "bidirectional"))
      (node (ref "Y2") (pin "P$1") (pinfunction "OSC0_P$1") (pintype "bidirectional"))
    )
    (net (code "58") (name "Net-(U20-OSC1)") (class "Default")
      (node (ref "R50") (pin "1") (pinfunction "1_1") (pintype "passive"))
      (node (ref "U20") (pin "P$41") (pinfunction "OSC1_P$41") (pintype "bidirectional"))
    )
    (net (code "59") (name "Net-(U20-PB1)") (class "Default")
      (node (ref "R28") (pin "1") (pinfunction "1_1") (pintype "passive"))
      (node (ref "R29") (pin "2") (pinfunction "2_2") (pintype "passive"))
      (node (ref "U20") (pin "P$46") (pinfunction "PB1_P$46") (pintype "bidirectional"))
    )
    (net (code "60") (name "Net-(U22B-S1)") (class "Default")
      (node (ref "C33") (pin "1") (pinfunction "1_1") (pintype "passive"))
      (node (ref "R34") (pin "2") (pinfunction "2_2") (pintype "passive"))
      (node (ref "U22") (pin "P10") (pinfunction "S5_P10") (pintype "passive"))
      (node (ref "U22") (pin "P11") (pinfunction "S6_P11") (pintype "passive"))
      (node (ref "U22") (pin "P6") (pinfunction "S1_P6") (pintype "passive"))
      (node (ref "U22") (pin "P7") (pinfunction "S2_P7") (pintype "passive"))
      (node (ref "U22") (pin "P8") (pinfunction "S3_P8") (pintype "passive"))
      (node (ref "U22") (pin "P9") (pinfunction "S4_P9") (pintype "passive"))
    )
    (net (code "61") (name "Net-(Y1-OSC0)") (class "Default")
      (node (ref "C45") (pin "1") (pinfunction "1_1") (pintype "passive"))
      (node (ref "R49") (pin "1") (pinfunction "1_1") (pintype "passive"))
      (node (ref "Y1") (pin "P$1") (pinfunction "OSC0_P$1") (pintype "bidirectional"))
    )
    (net (code "62") (name "Net-(Y2-OSC1)") (class "Default")
      (node (ref "C8") (pin "1") (pinfunction "1_1") (pintype "passive"))
      (node (ref "R50") (pin "2") (pinfunction "2_2") (pintype "passive"))
      (node (ref "Y2") (pin "P$3") (pinfunction "OSC1_P$3") (pintype "bidirectional"))
    )
    (net (code "63") (name "PA0") (class "Default")
      (node (ref "JP4") (pin "2") (pinfunction "2_2") (pintype "passive"))
      (node (ref "U1") (pin "P$33") (pinfunction "PA0_P$33") (pintype "bidirectional"))
      (node (ref "X11") (pin "74") (pinfunction "1_74") (pintype "passive"))
    )
    (net (code "64") (name "PA1") (class "Default")
      (node (ref "JP5") (pin "2") (pinfunction "2_2") (pintype "passive"))
      (node (ref "U1") (pin "P$34") (pinfunction "PA1_P$34") (pintype "bidirectional"))
      (node (ref "X11") (pin "76") (pinfunction "1_76") (pintype "passive"))
    )
    (net (code "65") (name "PA2") (class "Default")
      (node (ref "R20") (pin "2") (pinfunction "2_2") (pintype "passive"))
      (node (ref "U1") (pin "P$35") (pinfunction "PA2_P$35") (pintype "bidirectional"))
      (node (ref "X11") (pin "6") (pinfunction "1_6") (pintype "passive"))
    )
    (net (code "66") (name "PA3") (class "Default")
      (node (ref "R19") (pin "2") (pinfunction "2_2") (pintype "passive"))
      (node (ref "U1") (pin "P$36") (pinfunction "PA3_P$36") (pintype "bidirectional"))
      (node (ref "X11") (pin "8") (pinfunction "1_8") (pintype "passive"))
    )
    (net (code "67") (name "PA4") (class "Default")
      (node (ref "U1") (pin "P$37") (pinfunction "PA4_P$37") (pintype "bidirectional"))
      (node (ref "X11") (pin "10") (pinfunction "1_10") (pintype "passive"))
      (node (ref "X6") (pin "18") (pinfunction "1_18") (pintype "passive"))
    )
    (net (code "68") (name "PA5") (class "Default")
      (node (ref "U1") (pin "P$38") (pinfunction "PA5_P$38") (pintype "bidirectional"))
      (node (ref "X11") (pin "12") (pinfunction "1_12") (pintype "passive"))
      (node (ref "X6") (pin "20") (pinfunction "1_20") (pintype "passive"))
    )
    (net (code "69") (name "PA6") (class "Default")
      (node (ref "U1") (pin "P$40") (pinfunction "PA6_P$40") (pintype "bidirectional"))
      (node (ref "X11") (pin "25") (pinfunction "1_25") (pintype "passive"))
      (node (ref "X8") (pin "16") (pinfunction "1_16") (pintype "passive"))
    )
    (net (code "70") (name "PA7") (class "Default")
      (node (ref "U1") (pin "P$41") (pinfunction "PA7_P$41") (pintype "bidirectional"))
      (node (ref "X11") (pin "27") (pinfunction "1_27") (pintype "passive"))
      (node (ref "X7") (pin "8") (pinfunction "1_8") (pintype "passive"))
    )
    (net (code "71") (name "PB0") (class "Default")
      (node (ref "R18") (pin "1") (pinfunction "1_1") (pintype "passive"))
      (node (ref "U1") (pin "P$95") (pinfunction "PB0_P$95") (pintype "bidirectional"))
      (node (ref "X11") (pin "58") (pinfunction "1_58") (pintype "passive"))
    )
    (net (code "72") (name "PB2") (class "Default")
      (node (ref "U1") (pin "P$91") (pinfunction "PB2_P$91") (pintype "bidirectional"))
      (node (ref "X11") (pin "67") (pinfunction "1_67") (pintype "passive"))
      (node (ref "X8") (pin "17") (pinfunction "1_17") (pintype "passive"))
    )
    (net (code "73") (name "PB3") (class "Default")
      (node (ref "U1") (pin "P$92") (pinfunction "PB3_P$92") (pintype "bidirectional"))
      (node (ref "X11") (pin "69") (pinfunction "1_69") (pintype "passive"))
      (node (ref "X8") (pin "19") (pinfunction "1_19") (pintype "passive"))
    )
    (net (code "74") (name "PB4") (class "Default")
      (node (ref "U1") (pin "P$121") (pinfunction "PB4_P$121") (pintype "bidirectional"))
      (node (ref "X11") (pin "5") (pinfunction "1_5") (pintype "passive"))
      (node (ref "X6") (pin "6") (pinfunction "1_6") (pintype "passive"))
    )
    (net (code "75") (name "PB5") (class "Default")
      (node (ref "U1") (pin "P$120") (pinfunction "PB5_P$120") (pintype "bidirectional"))
      (node (ref "X11") (pin "7") (pinfunction "1_7") (pintype "passive"))
      (node (ref "X6") (pin "8") (pinfunction "1_8") (pintype "passive"))
    )
    (net (code "76") (name "PC4") (class "Default")
      (node (ref "U1") (pin "P$25") (pinfunction "PC4_P$25") (pintype "bidirectional"))
      (node (ref "X11") (pin "23") (pinfunction "1_23") (pintype "passive"))
      (node (ref "X8") (pin "5") (pinfunction "1_5") (pintype "passive"))
    )
    (net (code "77") (name "PC5") (class "Default")
      (node (ref "U1") (pin "P$24") (pinfunction "PC5_P$24") (pintype "bidirectional"))
      (node (ref "X11") (pin "21") (pinfunction "1_21") (pintype "passive"))
      (node (ref "X8") (pin "7") (pinfunction "1_7") (pintype "passive"))
    )
    (net (code "78") (name "PC6") (class "Default")
      (node (ref "U1") (pin "P$23") (pinfunction "PC6_P$23") (pintype "bidirectional"))
      (node (ref "X11") (pin "19") (pinfunction "1_19") (pintype "passive"))
      (node (ref "X8") (pin "9") (pinfunction "1_9") (pintype "passive"))
    )
    (net (code "79") (name "PC7") (class "Default")
      (node (ref "U1") (pin "P$22") (pinfunction "PC7_P$22") (pintype "bidirectional"))
      (node (ref "X11") (pin "17") (pinfunction "1_17") (pintype "passive"))
      (node (ref "X8") (pin "15") (pinfunction "1_15") (pintype "passive"))
    )
    (net (code "80") (name "PD0") (class "Default")
      (node (ref "U1") (pin "P$1") (pinfunction "PD0_P$1") (pintype "bidirectional"))
      (node (ref "X11") (pin "50") (pinfunction "1_50") (pintype "passive"))
      (node (ref "X9") (pin "14") (pinfunction "1_14") (pintype "passive"))
    )
    (net (code "81") (name "PD1") (class "Default")
      (node (ref "U1") (pin "P$2") (pinfunction "PD1_P$2") (pintype "bidirectional"))
      (node (ref "X11") (pin "48") (pinfunction "1_48") (pintype "passive"))
      (node (ref "X9") (pin "12") (pinfunction "1_12") (pintype "passive"))
    )
    (net (code "82") (name "PD2") (class "Default")
      (node (ref "U1") (pin "P$3") (pinfunction "PD2_P$3") (pintype "bidirectional"))
      (node (ref "X11") (pin "52") (pinfunction "1_52") (pintype "passive"))
      (node (ref "X6") (pin "3") (pinfunction "1_3") (pintype "passive"))
    )
    (net (code "83") (name "PD3") (class "Default")
      (node (ref "U1") (pin "P$4") (pinfunction "PD3_P$4") (pintype "bidirectional"))
      (node (ref "X11") (pin "46") (pinfunction "1_46") (pintype "passive"))
      (node (ref "X8") (pin "13") (pinfunction "1_13") (pintype "passive"))
    )
    (net (code "84") (name "PD4") (class "Default")
      (node (ref "JP4") (pin "3") (pinfunction "3_3") (pintype "passive"))
      (node (ref "U1") (pin "P$125") (pinfunction "PD4_P$125") (pintype "bidirectional"))
      (node (ref "X11") (pin "40") (pinfunction "1_40") (pintype "passive"))
    )
    (net (code "85") (name "PD5") (class "Default")
      (node (ref "JP5") (pin "3") (pinfunction "3_3") (pintype "passive"))
      (node (ref "U1") (pin "P$126") (pinfunction "PD5_P$126") (pintype "bidirectional"))
      (node (ref "X11") (pin "38") (pinfunction "1_38") (pintype "passive"))
    )
    (net (code "86") (name "PD6") (class "Default")
      (node (ref "U1") (pin "P$127") (pinfunction "PD6_P$127") (pintype "bidirectional"))
      (node (ref "U4") (pin "4") (pinfunction "*EN2_4") (pintype "input"))
      (node (ref "X11") (pin "44") (pinfunction "1_44") (pintype "passive"))
    )
    (net (code "87") (name "PD7") (class "Default")
      (node (ref "U1") (pin "P$128") (pinfunction "PD7_P$128") (pintype "bidirectional"))
      (node (ref "X11") (pin "42") (pinfunction "1_42") (pintype "passive"))
      (node (ref "X8") (pin "14") (pinfunction "1_14") (pintype "passive"))
    )
    (net (code "88") (name "PE0") (class "Default")
      (node (ref "U1") (pin "P$15") (pinfunction "PE0_P$15") (pintype "bidirectional"))
      (node (ref "X11") (pin "14") (pinfunction "1_14") (pintype "passive"))
      (node (ref "X8") (pin "6") (pinfunction "1_6") (pintype "passive"))
    )
    (net (code "89") (name "PE1") (class "Default")
      (node (ref "U1") (pin "P$14") (pinfunction "PE1_P$14") (pintype "bidirectional"))
      (node (ref "X11") (pin "16") (pinfunction "1_16") (pintype "passive"))
      (node (ref "X8") (pin "8") (pinfunction "1_8") (pintype "passive"))
    )
    (net (code "90") (name "PE2") (class "Default")
      (node (ref "U1") (pin "P$13") (pinfunction "PE2_P$13") (pintype "bidirectional"))
      (node (ref "X11") (pin "18") (pinfunction "1_18") (pintype "passive"))
      (node (ref "X8") (pin "10") (pinfunction "1_10") (pintype "passive"))
    )
    (net (code "91") (name "PE3") (class "Default")
      (node (ref "U1") (pin "P$12") (pinfunction "PE3_P$12") (pintype "bidirectional"))
      (node (ref "X11") (pin "20") (pinfunction "1_20") (pintype "passive"))
      (node (ref "X8") (pin "12") (pinfunction "1_12") (pintype "passive"))
    )
    (net (code "92") (name "PE4") (class "Default")
      (node (ref "U1") (pin "P$123") (pinfunction "PE4_P$123") (pintype "bidirectional"))
      (node (ref "X11") (pin "22") (pinfunction "1_22") (pintype "passive"))
      (node (ref "X8") (pin "3") (pinfunction "1_3") (pintype "passive"))
    )
    (net (code "93") (name "PE5") (class "Default")
      (node (ref "U1") (pin "P$124") (pinfunction "PE5_P$124") (pintype "bidirectional"))
      (node (ref "X11") (pin "24") (pinfunction "1_24") (pintype "passive"))
      (node (ref "X8") (pin "11") (pinfunction "1_11") (pintype "passive"))
    )
    (net (code "94") (name "PF0") (class "Default")
      (node (ref "D4") (pin "A") (pinfunction "A_A") (pintype "passive"))
      (node (ref "U1") (pin "P$42") (pinfunction "PF0_P$42") (pintype "bidirectional"))
      (node (ref "X11") (pin "66") (pinfunction "1_66") (pintype "passive"))
    )
    (net (code "95") (name "PF1") (class "Default")
      (node (ref "U1") (pin "P$43") (pinfunction "PF1_P$43") (pintype "bidirectional"))
      (node (ref "X11") (pin "68") (pinfunction "1_68") (pintype "passive"))
      (node (ref "X9") (pin "1") (pinfunction "1_1") (pintype "passive"))
    )
    (net (code "96") (name "PF2") (class "Default")
      (node (ref "U1") (pin "P$44") (pinfunction "PF2_P$44") (pintype "bidirectional"))
      (node (ref "X11") (pin "70") (pinfunction "1_70") (pintype "passive"))
      (node (ref "X9") (pin "3") (pinfunction "1_3") (pintype "passive"))
    )
    (net (code "97") (name "PF3") (class "Default")
      (node (ref "U1") (pin "P$45") (pinfunction "PF3_P$45") (pintype "bidirectional"))
      (node (ref "X11") (pin "72") (pinfunction "1_72") (pintype "passive"))
      (node (ref "X9") (pin "5") (pinfunction "1_5") (pintype "passive"))
    )
    (net (code "98") (name "PF4") (class "Default")
      (node (ref "D3") (pin "A") (pinfunction "A_A") (pintype "passive"))
      (node (ref "U1") (pin "P$46") (pinfunction "PF4_P$46") (pintype "bidirectional"))
      (node (ref "X11") (pin "64") (pinfunction "1_64") (pintype "passive"))
    )
    (net (code "99") (name "PG0") (class "Default")
      (node (ref "U1") (pin "P$49") (pinfunction "PG0_P$49") (pintype "bidirectional"))
      (node (ref "X11") (pin "31") (pinfunction "1_31") (pintype "passive"))
      (node (ref "X9") (pin "7") (pinfunction "1_7") (pintype "passive"))
    )
    (net (code "100") (name "PG1") (class "Default")
      (node (ref "U1") (pin "P$50") (pinfunction "PG1_P$50") (pintype "bidirectional"))
      (node (ref "X11") (pin "29") (pinfunction "1_29") (pintype "passive"))
      (node (ref "X7") (pin "1") (pinfunction "1_1") (pintype "passive"))
    )
    (net (code "101") (name "PH0") (class "Default")
      (node (ref "U1") (pin "P$29") (pinfunction "PH0_P$29") (pintype "bidirectional"))
      (node (ref "X11") (pin "9") (pinfunction "1_9") (pintype "passive"))
      (node (ref "X7") (pin "13") (pinfunction "1_13") (pintype "passive"))
    )
    (net (code "102") (name "PH1") (class "Default")
      (node (ref "U1") (pin "P$30") (pinfunction "PH1_P$30") (pintype "bidirectional"))
      (node (ref "X11") (pin "11") (pinfunction "1_11") (pintype "passive"))
      (node (ref "X7") (pin "15") (pinfunction "1_15") (pintype "passive"))
    )
    (net (code "103") (name "PH2") (class "Default")
      (node (ref "U1") (pin "P$31") (pinfunction "PH2_P$31") (pintype "bidirectional"))
      (node (ref "X11") (pin "13") (pinfunction "1_13") (pintype "passive"))
      (node (ref "X9") (pin "6") (pinfunction "1_6") (pintype "passive"))
    )
    (net (code "104") (name "PH3") (class "Default")
      (node (ref "U1") (pin "P$32") (pinfunction "PH3_P$32") (pintype "bidirectional"))
      (node (ref "X11") (pin "15") (pinfunction "1_15") (pintype "passive"))
      (node (ref "X9") (pin "8") (pinfunction "1_8") (pintype "passive"))
    )
    (net (code "105") (name "PJ0") (class "Default")
      (node (ref "U1") (pin "P$116") (pinfunction "PJ0_P$116") (pintype "bidirectional"))
      (node (ref "USR_SW1") (pin "P$1") (pinfunction "0_P$1") (pintype "passive"))
      (node (ref "USR_SW1") (pin "P$2") (pinfunction "0_P$2") (pintype "passive"))
      (node (ref "X11") (pin "82") (pinfunction "1_82") (pintype "passive"))
    )
    (net (code "106") (name "PJ1") (class "Default")
      (node (ref "U1") (pin "P$117") (pinfunction "PJ1_P$117") (pintype "bidirectional"))
      (node (ref "USR_SW2") (pin "P$1") (pinfunction "0_P$1") (pintype "passive"))
      (node (ref "USR_SW2") (pin "P$2") (pinfunction "0_P$2") (pintype "passive"))
      (node (ref "X11") (pin "84") (pinfunction "1_84") (pintype "passive"))
    )
    (net (code "107") (name "PK0") (class "Default")
      (node (ref "U1") (pin "P$18") (pinfunction "PK0_P$18") (pintype "bidirectional"))
      (node (ref "X11") (pin "26") (pinfunction "1_26") (pintype "passive"))
      (node (ref "X6") (pin "10") (pinfunction "1_10") (pintype "passive"))
    )
    (net (code "108") (name "PK1") (class "Default")
      (node (ref "U1") (pin "P$19") (pinfunction "PK1_P$19") (pintype "bidirectional"))
      (node (ref "X11") (pin "28") (pinfunction "1_28") (pintype "passive"))
      (node (ref "X6") (pin "12") (pinfunction "1_12") (pintype "passive"))
    )
    (net (code "109") (name "PK2") (class "Default")
      (node (ref "U1") (pin "P$20") (pinfunction "PK2_P$20") (pintype "bidirectional"))
      (node (ref "X11") (pin "30") (pinfunction "1_30") (pintype "passive"))
      (node (ref "X6") (pin "14") (pinfunction "1_14") (pintype "passive"))
    )
    (net (code "110") (name "PK3") (class "Default")
      (node (ref "U1") (pin "P$21") (pinfunction "PK3_P$21") (pintype "bidirectional"))
      (node (ref "X11") (pin "32") (pinfunction "1_32") (pintype "passive"))
      (node (ref "X6") (pin "16") (pinfunction "1_16") (pintype "passive"))
    )
    (net (code "111") (name "PK4") (class "Default")
      (node (ref "U1") (pin "P$63") (pinfunction "PK4_P$63") (pintype "bidirectional"))
      (node (ref "X11") (pin "77") (pinfunction "1_77") (pintype "passive"))
      (node (ref "X7") (pin "3") (pinfunction "1_3") (pintype "passive"))
    )
    (net (code "112") (name "PK5") (class "Default")
      (node (ref "U1") (pin "P$62") (pinfunction "PK5_P$62") (pintype "bidirectional"))
      (node (ref "X11") (pin "75") (pinfunction "1_75") (pintype "passive"))
      (node (ref "X7") (pin "5") (pinfunction "1_5") (pintype "passive"))
    )
    (net (code "113") (name "PK6") (class "Default")
      (node (ref "U1") (pin "P$61") (pinfunction "PK6_P$61") (pintype "bidirectional"))
      (node (ref "X11") (pin "63") (pinfunction "1_63") (pintype "passive"))
      (node (ref "X7") (pin "17") (pinfunction "1_17") (pintype "passive"))
    )
    (net (code "114") (name "PK7") (class "Default")
      (node (ref "U1") (pin "P$60") (pinfunction "PK7_P$60") (pintype "bidirectional"))
      (node (ref "X11") (pin "59") (pinfunction "1_59") (pintype "passive"))
      (node (ref "X7") (pin "19") (pinfunction "1_19") (pintype "passive"))
    )
    (net (code "115") (name "PL0") (class "Default")
      (node (ref "U1") (pin "P$81") (pinfunction "PL0_P$81") (pintype "bidirectional"))
      (node (ref "X11") (pin "43") (pinfunction "1_43") (pintype "passive"))
      (node (ref "X9") (pin "13") (pinfunction "1_13") (pintype "passive"))
    )
    (net (code "116") (name "PL1") (class "Default")
      (node (ref "U1") (pin "P$82") (pinfunction "PL1_P$82") (pintype "bidirectional"))
      (node (ref "X11") (pin "45") (pinfunction "1_45") (pintype "passive"))
      (node (ref "X9") (pin "15") (pinfunction "1_15") (pintype "passive"))
    )
    (net (code "117") (name "PL2") (class "Default")
      (node (ref "U1") (pin "P$83") (pinfunction "PL2_P$83") (pintype "bidirectional"))
      (node (ref "X11") (pin "47") (pinfunction "1_47") (pintype "passive"))
      (node (ref "X9") (pin "17") (pinfunction "1_17") (pintype "passive"))
    )
    (net (code "118") (name "PL3") (class "Default")
      (node (ref "U1") (pin "P$84") (pinfunction "PL3_P$84") (pintype "bidirectional"))
      (node (ref "X11") (pin "49") (pinfunction "1_49") (pintype "passive"))
      (node (ref "X9") (pin "19") (pinfunction "1_19") (pintype "passive"))
    )
    (net (code "119") (name "PL4") (class "Default")
      (node (ref "U1") (pin "P$85") (pinfunction "PL4_P$85") (pintype "bidirectional"))
      (node (ref "X11") (pin "65") (pinfunction "1_65") (pintype "passive"))
      (node (ref "X9") (pin "9") (pinfunction "1_9") (pintype "passive"))
    )
    (net (code "120") (name "PL5") (class "Default")
      (node (ref "U1") (pin "P$86") (pinfunction "PL5_P$86") (pintype "bidirectional"))
      (node (ref "X11") (pin "79") (pinfunction "1_79") (pintype "passive"))
      (node (ref "X9") (pin "11") (pinfunction "1_11") (pintype "passive"))
    )
    (net (code "121") (name "PM0") (class "Default")
      (node (ref "U1") (pin "P$78") (pinfunction "PM0_P$78") (pintype "bidirectional"))
      (node (ref "X11") (pin "41") (pinfunction "1_41") (pintype "passive"))
      (node (ref "X7") (pin "7") (pinfunction "1_7") (pintype "passive"))
    )
    (net (code "122") (name "PM1") (class "Default")
      (node (ref "U1") (pin "P$77") (pinfunction "PM1_P$77") (pintype "bidirectional"))
      (node (ref "X11") (pin "39") (pinfunction "1_39") (pintype "passive"))
      (node (ref "X7") (pin "9") (pinfunction "1_9") (pintype "passive"))
    )
    (net (code "123") (name "PM2") (class "Default")
      (node (ref "U1") (pin "P$76") (pinfunction "PM2_P$76") (pintype "bidirectional"))
      (node (ref "X11") (pin "37") (pinfunction "1_37") (pintype "passive"))
      (node (ref "X7") (pin "11") (pinfunction "1_11") (pintype "passive"))
    )
    (net (code "124") (name "PM3") (class "Default")
      (node (ref "U1") (pin "P$75") (pinfunction "PM3_P$75") (pintype "bidirectional"))
      (node (ref "X11") (pin "33") (pinfunction "1_33") (pintype "passive"))
      (node (ref "X9") (pin "4") (pinfunction "1_4") (pintype "passive"))
    )
    (net (code "125") (name "PM4") (class "Default")
      (node (ref "U1") (pin "P$74") (pinfunction "PM4_P$74") (pintype "bidirectional"))
      (node (ref "X11") (pin "92") (pinfunction "1_92") (pintype "passive"))
      (node (ref "X8") (pin "18") (pinfunction "1_18") (pintype "passive"))
    )
    (net (code "126") (name "PM5") (class "Default")
      (node (ref "U1") (pin "P$73") (pinfunction "PM5_P$73") (pintype "bidirectional"))
      (node (ref "X11") (pin "90") (pinfunction "1_90") (pintype "passive"))
      (node (ref "X8") (pin "20") (pinfunction "1_20") (pintype "passive"))
    )
    (net (code "127") (name "PM6") (class "Default")
      (node (ref "U1") (pin "P$72") (pinfunction "PM6_P$72") (pintype "bidirectional"))
      (node (ref "X11") (pin "88") (pinfunction "1_88") (pintype "passive"))
      (node (ref "X7") (pin "20") (pinfunction "1_20") (pintype "passive"))
    )
    (net (code "128") (name "PM7") (class "Default")
      (node (ref "U1") (pin "P$71") (pinfunction "PM7_P$71") (pintype "bidirectional"))
      (node (ref "X11") (pin "86") (pinfunction "1_86") (pintype "passive"))
      (node (ref "X7") (pin "4") (pinfunction "1_4") (pintype "passive"))
    )
    (net (code "129") (name "PN0") (class "Default")
      (node (ref "D2") (pin "A") (pinfunction "A_A") (pintype "passive"))
      (node (ref "U1") (pin "P$107") (pinfunction "PN0_P$107") (pintype "bidirectional"))
      (node (ref "X11") (pin "85") (pinfunction "1_85") (pintype "passive"))
    )
    (net (code "130") (name "PN1") (class "Default")
      (node (ref "D1") (pin "A") (pinfunction "A_A") (pintype "passive"))
      (node (ref "U1") (pin "P$108") (pinfunction "PN1_P$108") (pintype "bidirectional"))
      (node (ref "X11") (pin "87") (pinfunction "1_87") (pintype "passive"))
    )
    (net (code "131") (name "PN2") (class "Default")
      (node (ref "U1") (pin "P$109") (pinfunction "PN2_P$109") (pintype "bidirectional"))
      (node (ref "X11") (pin "89") (pinfunction "1_89") (pintype "passive"))
      (node (ref "X9") (pin "16") (pinfunction "1_16") (pintype "passive"))
    )
    (net (code "132") (name "PN3") (class "Default")
      (node (ref "U1") (pin "P$110") (pinfunction "PN3_P$110") (pintype "bidirectional"))
      (node (ref "X11") (pin "91") (pinfunction "1_91") (pintype "passive"))
      (node (ref "X9") (pin "18") (pinfunction "1_18") (pintype "passive"))
    )
    (net (code "133") (name "PN4") (class "Default")
      (node (ref "U1") (pin "P$111") (pinfunction "PN4_P$111") (pintype "bidirectional"))
      (node (ref "X11") (pin "81") (pinfunction "1_81") (pintype "passive"))
      (node (ref "X6") (pin "19") (pinfunction "1_19") (pintype "passive"))
    )
    (net (code "134") (name "PN5") (class "Default")
      (node (ref "U1") (pin "P$112") (pinfunction "PN5_P$112") (pintype "bidirectional"))
      (node (ref "X11") (pin "83") (pinfunction "1_83") (pintype "passive"))
      (node (ref "X6") (pin "17") (pinfunction "1_17") (pintype "passive"))
    )
    (net (code "135") (name "PP0") (class "Default")
      (node (ref "U1") (pin "P$118") (pinfunction "PP0_P$118") (pintype "bidirectional"))
      (node (ref "X11") (pin "54") (pinfunction "1_54") (pintype "passive"))
      (node (ref "X6") (pin "5") (pinfunction "1_5") (pintype "passive"))
    )
    (net (code "136") (name "PP1") (class "Default")
      (node (ref "U1") (pin "P$119") (pinfunction "PP1_P$119") (pintype "bidirectional"))
      (node (ref "X11") (pin "56") (pinfunction "1_56") (pintype "passive"))
      (node (ref "X6") (pin "7") (pinfunction "1_7") (pintype "passive"))
    )
    (net (code "137") (name "PP2") (class "Default")
      (node (ref "U1") (pin "P$103") (pinfunction "PP2_P$103") (pintype "bidirectional"))
      (node (ref "X11") (pin "71") (pinfunction "1_71") (pintype "passive"))
      (node (ref "X9") (pin "20") (pinfunction "1_20") (pintype "passive"))
    )
    (net (code "138") (name "PP3") (class "Default")
      (node (ref "U1") (pin "P$104") (pinfunction "PP3_P$104") (pintype "bidirectional"))
      (node (ref "X11") (pin "73") (pinfunction "1_73") (pintype "passive"))
      (node (ref "X7") (pin "16") (pinfunction "1_16") (pintype "passive"))
    )
    (net (code "139") (name "PP4") (class "Default")
      (node (ref "U1") (pin "P$105") (pinfunction "PP4_P$105") (pintype "bidirectional"))
      (node (ref "X11") (pin "78") (pinfunction "1_78") (pintype "passive"))
      (node (ref "X6") (pin "15") (pinfunction "1_15") (pintype "passive"))
    )
    (net (code "140") (name "PP5") (class "Default")
      (node (ref "U1") (pin "P$106") (pinfunction "PP5_P$106") (pintype "bidirectional"))
      (node (ref "X11") (pin "80") (pinfunction "1_80") (pintype "passive"))
      (node (ref "X7") (pin "6") (pinfunction "1_6") (pintype "passive"))
    )
    (net (code "141") (name "PQ0") (class "Default")
      (node (ref "U1") (pin "P$5") (pinfunction "PQ0_P$5") (pintype "bidirectional"))
      (node (ref "X11") (pin "51") (pinfunction "1_51") (pintype "passive"))
      (node (ref "X6") (pin "13") (pinfunction "1_13") (pintype "passive"))
    )
    (net (code "142") (name "PQ1") (class "Default")
      (node (ref "U1") (pin "P$6") (pinfunction "PQ1_P$6") (pintype "bidirectional"))
      (node (ref "X11") (pin "53") (pinfunction "1_53") (pintype "passive"))
      (node (ref "X7") (pin "18") (pinfunction "1_18") (pintype "passive"))
    )
    (net (code "143") (name "PQ2") (class "Default")
      (node (ref "R19") (pin "1") (pinfunction "1_1") (pintype "passive"))
      (node (ref "U1") (pin "P$11") (pinfunction "PQ2_P$11") (pintype "bidirectional"))
      (node (ref "X11") (pin "55") (pinfunction "1_55") (pintype "passive"))
      (node (ref "X7") (pin "12") (pinfunction "1_12") (pintype "passive"))
    )
    (net (code "144") (name "PQ3") (class "Default")
      (node (ref "R20") (pin "1") (pinfunction "1_1") (pintype "passive"))
      (node (ref "U1") (pin "P$27") (pinfunction "PQ3_P$27") (pintype "bidirectional"))
      (node (ref "X11") (pin "57") (pinfunction "1_57") (pintype "passive"))
      (node (ref "X7") (pin "14") (pinfunction "1_14") (pintype "passive"))
    )
    (net (code "145") (name "PQ4") (class "Default")
      (node (ref "U1") (pin "P$102") (pinfunction "PQ4_P$102") (pintype "bidirectional"))
      (node (ref "U4") (pin "5") (pinfunction "*OC2_5") (pintype "output"))
      (node (ref "X11") (pin "93") (pinfunction "1_93") (pintype "passive"))
    )
    (net (code "146") (name "RBIAS") (class "Default")
      (node (ref "R25") (pin "1") (pinfunction "1_1") (pintype "passive"))
      (node (ref "U1") (pin "P$59") (pinfunction "RBIAS_P$59") (pintype "bidirectional"))
    )
    (net (code "147") (name "TARGET_ID") (class "Default")
      (node (ref "R18") (pin "2") (pinfunction "2_2") (pintype "passive"))
      (node (ref "TP7") (pin "TP") (pinfunction "TP_TP") (pintype "input"))
      (node (ref "U2") (pin "2") (pinfunction "D-_2") (pintype "passive"))
      (node (ref "U7") (pin "P4") (pinfunction "ID_P4") (pintype "bidirectional"))
    )
    (net (code "148") (name "TARGET_RXD") (class "Default")
      (node (ref "JP4") (pin "1") (pinfunction "1_1") (pintype "passive"))
      (node (ref "R7") (pin "1") (pinfunction "1_1") (pintype "passive"))
      (node (ref "X1") (pin "12") (pinfunction "1_12") (pintype "passive"))
    )
    (net (code "149") (name "TARGET_TCK{slash}SWCLK") (class "Default")
      (node (ref "R1") (pin "2") (pinfunction "2_2") (pintype "passive"))
      (node (ref "R8") (pin "1") (pinfunction "1_1") (pintype "passive"))
      (node (ref "U1") (pin "P$100") (pinfunction "PC0_P$100") (pintype "bidirectional"))
      (node (ref "X1") (pin "10") (pinfunction "1_10") (pintype "passive"))
    )
    (net (code "150") (name "TARGET_TDI") (class "Default")
      (node (ref "R11") (pin "1") (pinfunction "1_1") (pintype "passive"))
      (node (ref "U1") (pin "P$98") (pinfunction "PC2_P$98") (pintype "bidirectional"))
      (node (ref "X1") (pin "6") (pinfunction "1_6") (pintype "passive"))
    )
    (net (code "151") (name "TARGET_TDO{slash}SWO") (class "Default")
      (node (ref "R15") (pin "1") (pinfunction "1_1") (pintype "passive"))
      (node (ref "U1") (pin "P$97") (pinfunction "PC3_P$97") (pintype "bidirectional"))
      (node (ref "X1") (pin "4") (pinfunction "1_4") (pintype "passive"))
    )
    (net (code "152") (name "TARGET_TMS{slash}SWDIO") (class "Default")
      (node (ref "R10") (pin "1") (pinfunction "1_1") (pintype "passive"))
      (node (ref "R2") (pin "2") (pinfunction "2_2") (pintype "passive"))
      (node (ref "U1") (pin "P$99") (pinfunction "PC1_P$99") (pintype "bidirectional"))
      (node (ref "X1") (pin "8") (pinfunction "1_8") (pintype "passive"))
    )
    (net (code "153") (name "TARGET_TXD") (class "Default")
      (node (ref "JP5") (pin "1") (pinfunction "1_1") (pintype "passive"))
      (node (ref "R6") (pin "1") (pinfunction "1_1") (pintype "passive"))
      (node (ref "X1") (pin "14") (pinfunction "1_14") (pintype "passive"))
    )
    (net (code "154") (name "TARGET_VBUS") (class "Default")
      (node (ref "JP1") (pin "3") (pinfunction "3_3") (pintype "passive"))
      (node (ref "TP4") (pin "TP") (pinfunction "TP_TP") (pintype "input"))
      (node (ref "U1") (pin "P$96") (pinfunction "PB1_P$96") (pintype "bidirectional"))
      (node (ref "U2") (pin "6") (pinfunction "VBUS_6") (pintype "passive"))
      (node (ref "U4") (pin "6") (pinfunction "OUT2_6") (pintype "output"))
      (node (ref "U7") (pin "P1") (pinfunction "VBUS_P1") (pintype "bidirectional"))
      (node (ref "X11") (pin "60") (pinfunction "1_60") (pintype "passive"))
    )
    (net (code "155") (name "USBD_N") (class "Default")
      (node (ref "TP5") (pin "TP") (pinfunction "TP_TP") (pintype "input"))
      (node (ref "U1") (pin "P$93") (pinfunction "PL7_P$93") (pintype "bidirectional"))
      (node (ref "U2") (pin "1") (pinfunction "D+_1") (pintype "passive"))
      (node (ref "U7") (pin "P2") (pinfunction "DM_P2") (pintype "bidirectional"))
    )
    (net (code "156") (name "USBD_P") (class "Default")
      (node (ref "TP6") (pin "TP") (pinfunction "TP_TP") (pintype "input"))
      (node (ref "U1") (pin "P$94") (pinfunction "PL6_P$94") (pintype "bidirectional"))
      (node (ref "U2") (pin "3") (pinfunction "ID_3") (pintype "passive"))
      (node (ref "U7") (pin "P3") (pinfunction "DP_P3") (pintype "bidirectional"))
    )
    (net (code "157") (name "VBUS") (class "Default")
      (node (ref "JP1") (pin "2") (pinfunction "2_2") (pintype "passive"))
      (node (ref "JP1") (pin "4") (pinfunction "4_4") (pintype "passive"))
      (node (ref "JP1") (pin "6") (pinfunction "6_6") (pintype "passive"))
      (node (ref "R35") (pin "1") (pinfunction "1_1") (pintype "passive"))
      (node (ref "R36") (pin "2") (pinfunction "2_2") (pintype "passive"))
      (node (ref "U4") (pin "2") (pinfunction "IN_2") (pintype "input"))
    )
    (net (code "158") (name "VCP_RXD") (class "Default")
      (node (ref "R6") (pin "2") (pinfunction "2_2") (pintype "passive"))
      (node (ref "U20") (pin "P$17") (pinfunction "PA0_P$17") (pintype "bidirectional"))
      (node (ref "X1") (pin "13") (pinfunction "1_13") (pintype "passive"))
    )
    (net (code "159") (name "VCP_TXD") (class "Default")
      (node (ref "R7") (pin "2") (pinfunction "2_2") (pintype "passive"))
      (node (ref "U20") (pin "P$18") (pinfunction "PA1_P$18") (pintype "bidirectional"))
      (node (ref "X1") (pin "11") (pinfunction "1_11") (pintype "passive"))
    )
    (net (code "160") (name "VERSION_0") (class "Default")
      (node (ref "R12") (pin "1") (pinfunction "1_1") (pintype "passive"))
      (node (ref "U20") (pin "P$61") (pinfunction "PD0_P$61") (pintype "bidirectional"))
    )
    (net (code "161") (name "VERSION_1") (class "Default")
      (node (ref "R13") (pin "1") (pinfunction "1_1") (pintype "passive"))
      (node (ref "U20") (pin "P$47") (pinfunction "PB2_P$47") (pintype "bidirectional"))
    )
    (net (code "162") (name "VERSION_2") (class "Default")
      (node (ref "R14") (pin "1") (pinfunction "1_1") (pintype "passive"))
      (node (ref "U20") (pin "P$48") (pinfunction "PB3_P$48") (pintype "bidirectional"))
    )
    (net (code "163") (name "VREF+") (class "Default")
      (node (ref "R41") (pin "1") (pinfunction "1_1") (pintype "passive"))
      (node (ref "TP13") (pin "TP") (pinfunction "TP_TP") (pintype "input"))
      (node (ref "U1") (pin "P$9") (pinfunction "VREFA+_P$9") (pintype "bidirectional"))
      (node (ref "X11") (pin "34") (pinfunction "1_34") (pintype "passive"))
    )
    (net (code "164") (name "unconnected-(JP1-Pad1)") (class "Default")
      (node (ref "JP1") (pin "1") (pinfunction "1_1") (pintype "passive"))
    )
    (net (code "165") (name "unconnected-(U2-N.C.-Pad5)") (class "Default")
      (node (ref "U2") (pin "5") (pinfunction "N.C._5") (pintype "no_connect"))
    )
    (net (code "166") (name "unconnected-(U3-ID-Pad3)") (class "Default")
      (node (ref "U3") (pin "3") (pinfunction "ID_3") (pintype "passive"))
    )
    (net (code "167") (name "unconnected-(U3-N.C.-Pad5)") (class "Default")
      (node (ref "U3") (pin "5") (pinfunction "N.C._5") (pintype "no_connect"))
    )
    (net (code "168") (name "unconnected-(U5-NC-Pad5)") (class "Default")
      (node (ref "U5") (pin "5") (pinfunction "NC_5") (pintype "passive"))
    )
    (net (code "169") (name "unconnected-(U6-P$7-PadP7)") (class "Default")
      (node (ref "U6") (pin "P7") (pinfunction "P$7_P7") (pintype "bidirectional"))
    )
    (net (code "170") (name "unconnected-(U20-PB0-PadP$45)") (class "Default")
      (node (ref "U20") (pin "P$45") (pinfunction "PB0_P$45") (pintype "bidirectional"))
    )
    (net (code "171") (name "unconnected-(U20-PB4-PadP$58)") (class "Default")
      (node (ref "U20") (pin "P$58") (pinfunction "PB4_P$58") (pintype "bidirectional"))
    )
    (net (code "172") (name "unconnected-(U20-PB5-PadP$57)") (class "Default")
      (node (ref "U20") (pin "P$57") (pinfunction "PB5_P$57") (pintype "bidirectional"))
    )
    (net (code "173") (name "unconnected-(U20-PB6-PadP$1)") (class "Default")
      (node (ref "U20") (pin "P$1") (pinfunction "PB6_P$1") (pintype "bidirectional"))
    )
    (net (code "174") (name "unconnected-(U20-PB7-PadP$4)") (class "Default")
      (node (ref "U20") (pin "P$4") (pinfunction "PB7_P$4") (pintype "bidirectional"))
    )
    (net (code "175") (name "unconnected-(U20-PC4-PadP$16)") (class "Default")
      (node (ref "U20") (pin "P$16") (pinfunction "PC4_P$16") (pintype "bidirectional"))
    )
    (net (code "176") (name "unconnected-(U20-PC5-PadP$15)") (class "Default")
      (node (ref "U20") (pin "P$15") (pinfunction "PC5_P$15") (pintype "bidirectional"))
    )
    (net (code "177") (name "unconnected-(U20-PC6-PadP$14)") (class "Default")
      (node (ref "U20") (pin "P$14") (pinfunction "PC6_P$14") (pintype "bidirectional"))
    )
    (net (code "178") (name "unconnected-(U20-PC7-PadP$13)") (class "Default")
      (node (ref "U20") (pin "P$13") (pinfunction "PC7_P$13") (pintype "bidirectional"))
    )
    (net (code "179") (name "unconnected-(U20-PD1-PadP$62)") (class "Default")
      (node (ref "U20") (pin "P$62") (pinfunction "PD1_P$62") (pintype "bidirectional"))
    )
    (net (code "180") (name "unconnected-(U20-PD2-PadP$63)") (class "Default")
      (node (ref "U20") (pin "P$63") (pinfunction "PD2_P$63") (pintype "bidirectional"))
    )
    (net (code "181") (name "unconnected-(U20-PD7-PadP$10)") (class "Default")
      (node (ref "U20") (pin "P$10") (pinfunction "PD7_P$10") (pintype "bidirectional"))
    )
    (net (code "182") (name "unconnected-(U20-PE0-PadP$9)") (class "Default")
      (node (ref "U20") (pin "P$9") (pinfunction "PE0_P$9") (pintype "bidirectional"))
    )
    (net (code "183") (name "unconnected-(U20-PE1-PadP$8)") (class "Default")
      (node (ref "U20") (pin "P$8") (pinfunction "PE1_P$8") (pintype "bidirectional"))
    )
    (net (code "184") (name "unconnected-(U20-PE2-PadP$7)") (class "Default")
      (node (ref "U20") (pin "P$7") (pinfunction "PE2_P$7") (pintype "bidirectional"))
    )
    (net (code "185") (name "unconnected-(U20-PE3-PadP$6)") (class "Default")
      (node (ref "U20") (pin "P$6") (pinfunction "PE3_P$6") (pintype "bidirectional"))
    )
    (net (code "186") (name "unconnected-(U20-PE4-PadP$59)") (class "Default")
      (node (ref "U20") (pin "P$59") (pinfunction "PE4_P$59") (pintype "bidirectional"))
    )
    (net (code "187") (name "unconnected-(U20-PE5-PadP$60)") (class "Default")
      (node (ref "U20") (pin "P$60") (pinfunction "PE5_P$60") (pintype "bidirectional"))
    )
    (net (code "188") (name "unconnected-(U20-PF0-PadP$28)") (class "Default")
      (node (ref "U20") (pin "P$28") (pinfunction "PF0_P$28") (pintype "bidirectional"))
    )
    (net (code "189") (name "unconnected-(U20-PF3-PadP$31)") (class "Default")
      (node (ref "U20") (pin "P$31") (pinfunction "PF3_P$31") (pintype "bidirectional"))
    )
    (net (code "190") (name "unconnected-(U20-PF4-PadP$5)") (class "Default")
      (node (ref "U20") (pin "P$5") (pinfunction "PF4_P$5") (pintype "bidirectional"))
    )
    (net (code "191") (name "unconnected-(U20-XOSC1-PadP$36)") (class "Default")
      (node (ref "U20") (pin "P$36") (pinfunction "XOSC1_P$36") (pintype "bidirectional"))
    )
    (net (code "192") (name "unconnected-(U20-~{HIB}-PadP$33)") (class "Default")
      (node (ref "U20") (pin "P$33") (pinfunction "~{HIB}_P$33") (pintype "bidirectional"))
    )
    (net (code "193") (name "unconnected-(U21-RTCK-Pad7)") (class "Default")
      (node (ref "U21") (pin "7") (pinfunction "RTCK_7") (pintype "bidirectional"))
    )
    (net (code "194") (name "unconnected-(U22A-ID-PadP4)") (class "Default")
      (node (ref "U22") (pin "P4") (pinfunction "ID_P4") (pintype "bidirectional"))
    )
    (net (code "195") (name "unconnected-(Y1-NC2-PadP$2)") (class "Default")
      (node (ref "Y1") (pin "P$2") (pinfunction "NC2_P$2") (pintype "bidirectional"))
    )
    (net (code "196") (name "unconnected-(Y1-NC4-PadP$4)") (class "Default")
      (node (ref "Y1") (pin "P$4") (pinfunction "NC4_P$4") (pintype "bidirectional"))
    )
    (net (code "197") (name "unconnected-(Y2-NC2-PadP$2)") (class "Default")
      (node (ref "Y2") (pin "P$2") (pinfunction "NC2_P$2") (pintype "bidirectional"))
    )
    (net (code "198") (name "unconnected-(Y2-NC4-PadP$4)") (class "Default")
      (node (ref "Y2") (pin "P$4") (pinfunction "NC4_P$4") (pintype "bidirectional"))
    )
    (net (code "199") (name "~{DEBUG_RESET_OUT}") (class "Default")
      (node (ref "R16") (pin "2") (pinfunction "2_2") (pintype "passive"))
      (node (ref "U20") (pin "P$23") (pinfunction "PA6_P$23") (pintype "bidirectional"))
      (node (ref "U6") (pin "P10") (pinfunction "~{RESET}_P10") (pintype "bidirectional"))
      (node (ref "X1") (pin "1") (pinfunction "1_1") (pintype "passive"))
    )
    (net (code "200") (name "~{EXTERNAL_DEBUG}") (class "Default")
      (node (ref "R40") (pin "1") (pinfunction "1_1") (pintype "passive"))
      (node (ref "TP2") (pin "TP") (pinfunction "TP_TP") (pintype "input"))
      (node (ref "U20") (pin "P$24") (pinfunction "PA7_P$24") (pintype "bidirectional"))
    )
    (net (code "201") (name "~{TARGET_RESET}") (class "Default")
      (node (ref "R16") (pin "1") (pinfunction "1_1") (pintype "passive"))
      (node (ref "R51") (pin "1") (pinfunction "1_1") (pintype "passive"))
      (node (ref "RESET") (pin "P$3") (pinfunction "1_P$3") (pintype "passive"))
      (node (ref "RESET") (pin "P$4") (pinfunction "1_P$4") (pintype "passive"))
      (node (ref "X1") (pin "2") (pinfunction "1_2") (pintype "passive"))
      (node (ref "X11") (pin "94") (pinfunction "1_94") (pintype "passive"))
      (node (ref "X7") (pin "10") (pinfunction "1_10") (pintype "passive"))
      (node (ref "X9") (pin "10") (pinfunction "1_10") (pintype "passive"))
    )
    (net (code "202") (name "~{WAKE}") (class "Default")
      (node (ref "R42") (pin "2") (pinfunction "2_2") (pintype "passive"))
      (node (ref "TP10") (pin "TP") (pinfunction "TP_TP") (pintype "input"))
      (node (ref "U1") (pin "P$64") (pinfunction "~{WAKE}_P$64") (pintype "bidirectional"))
      (node (ref "WAKE") (pin "P$1") (pinfunction "0_P$1") (pintype "passive"))
      (node (ref "WAKE") (pin "P$2") (pinfunction "0_P$2") (pintype "passive"))
      (node (ref "X11") (pin "95") (pinfunction "1_95") (pintype "passive"))
    )
  )
)
